# Omniband.net
KiCad netlist of a schematic drawn in EAGLE
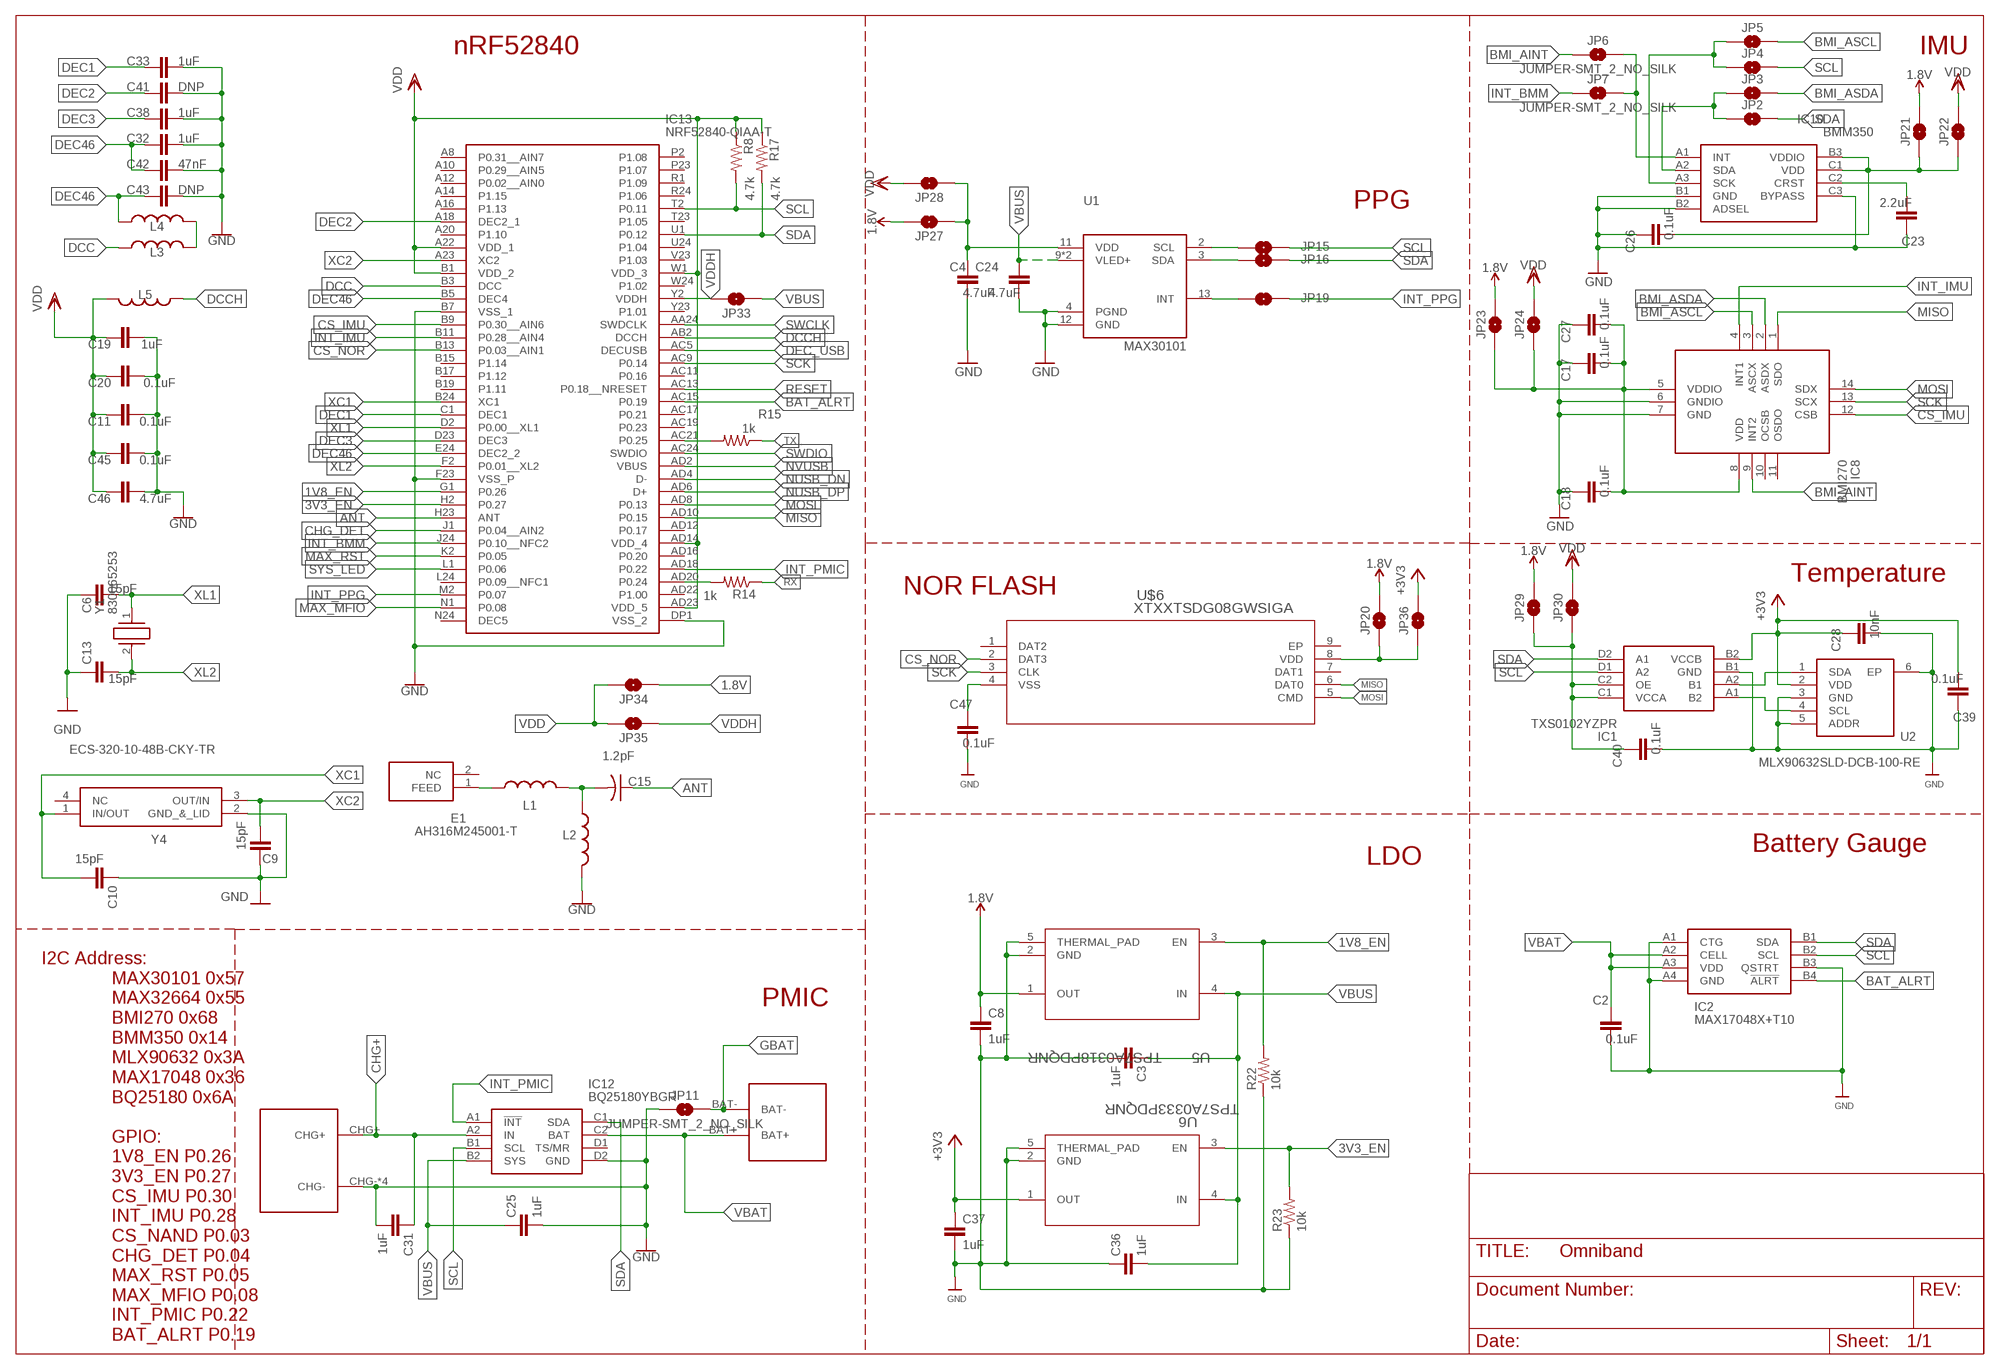
[diagram p0: schematic, sheet 1, part 1 of 2]
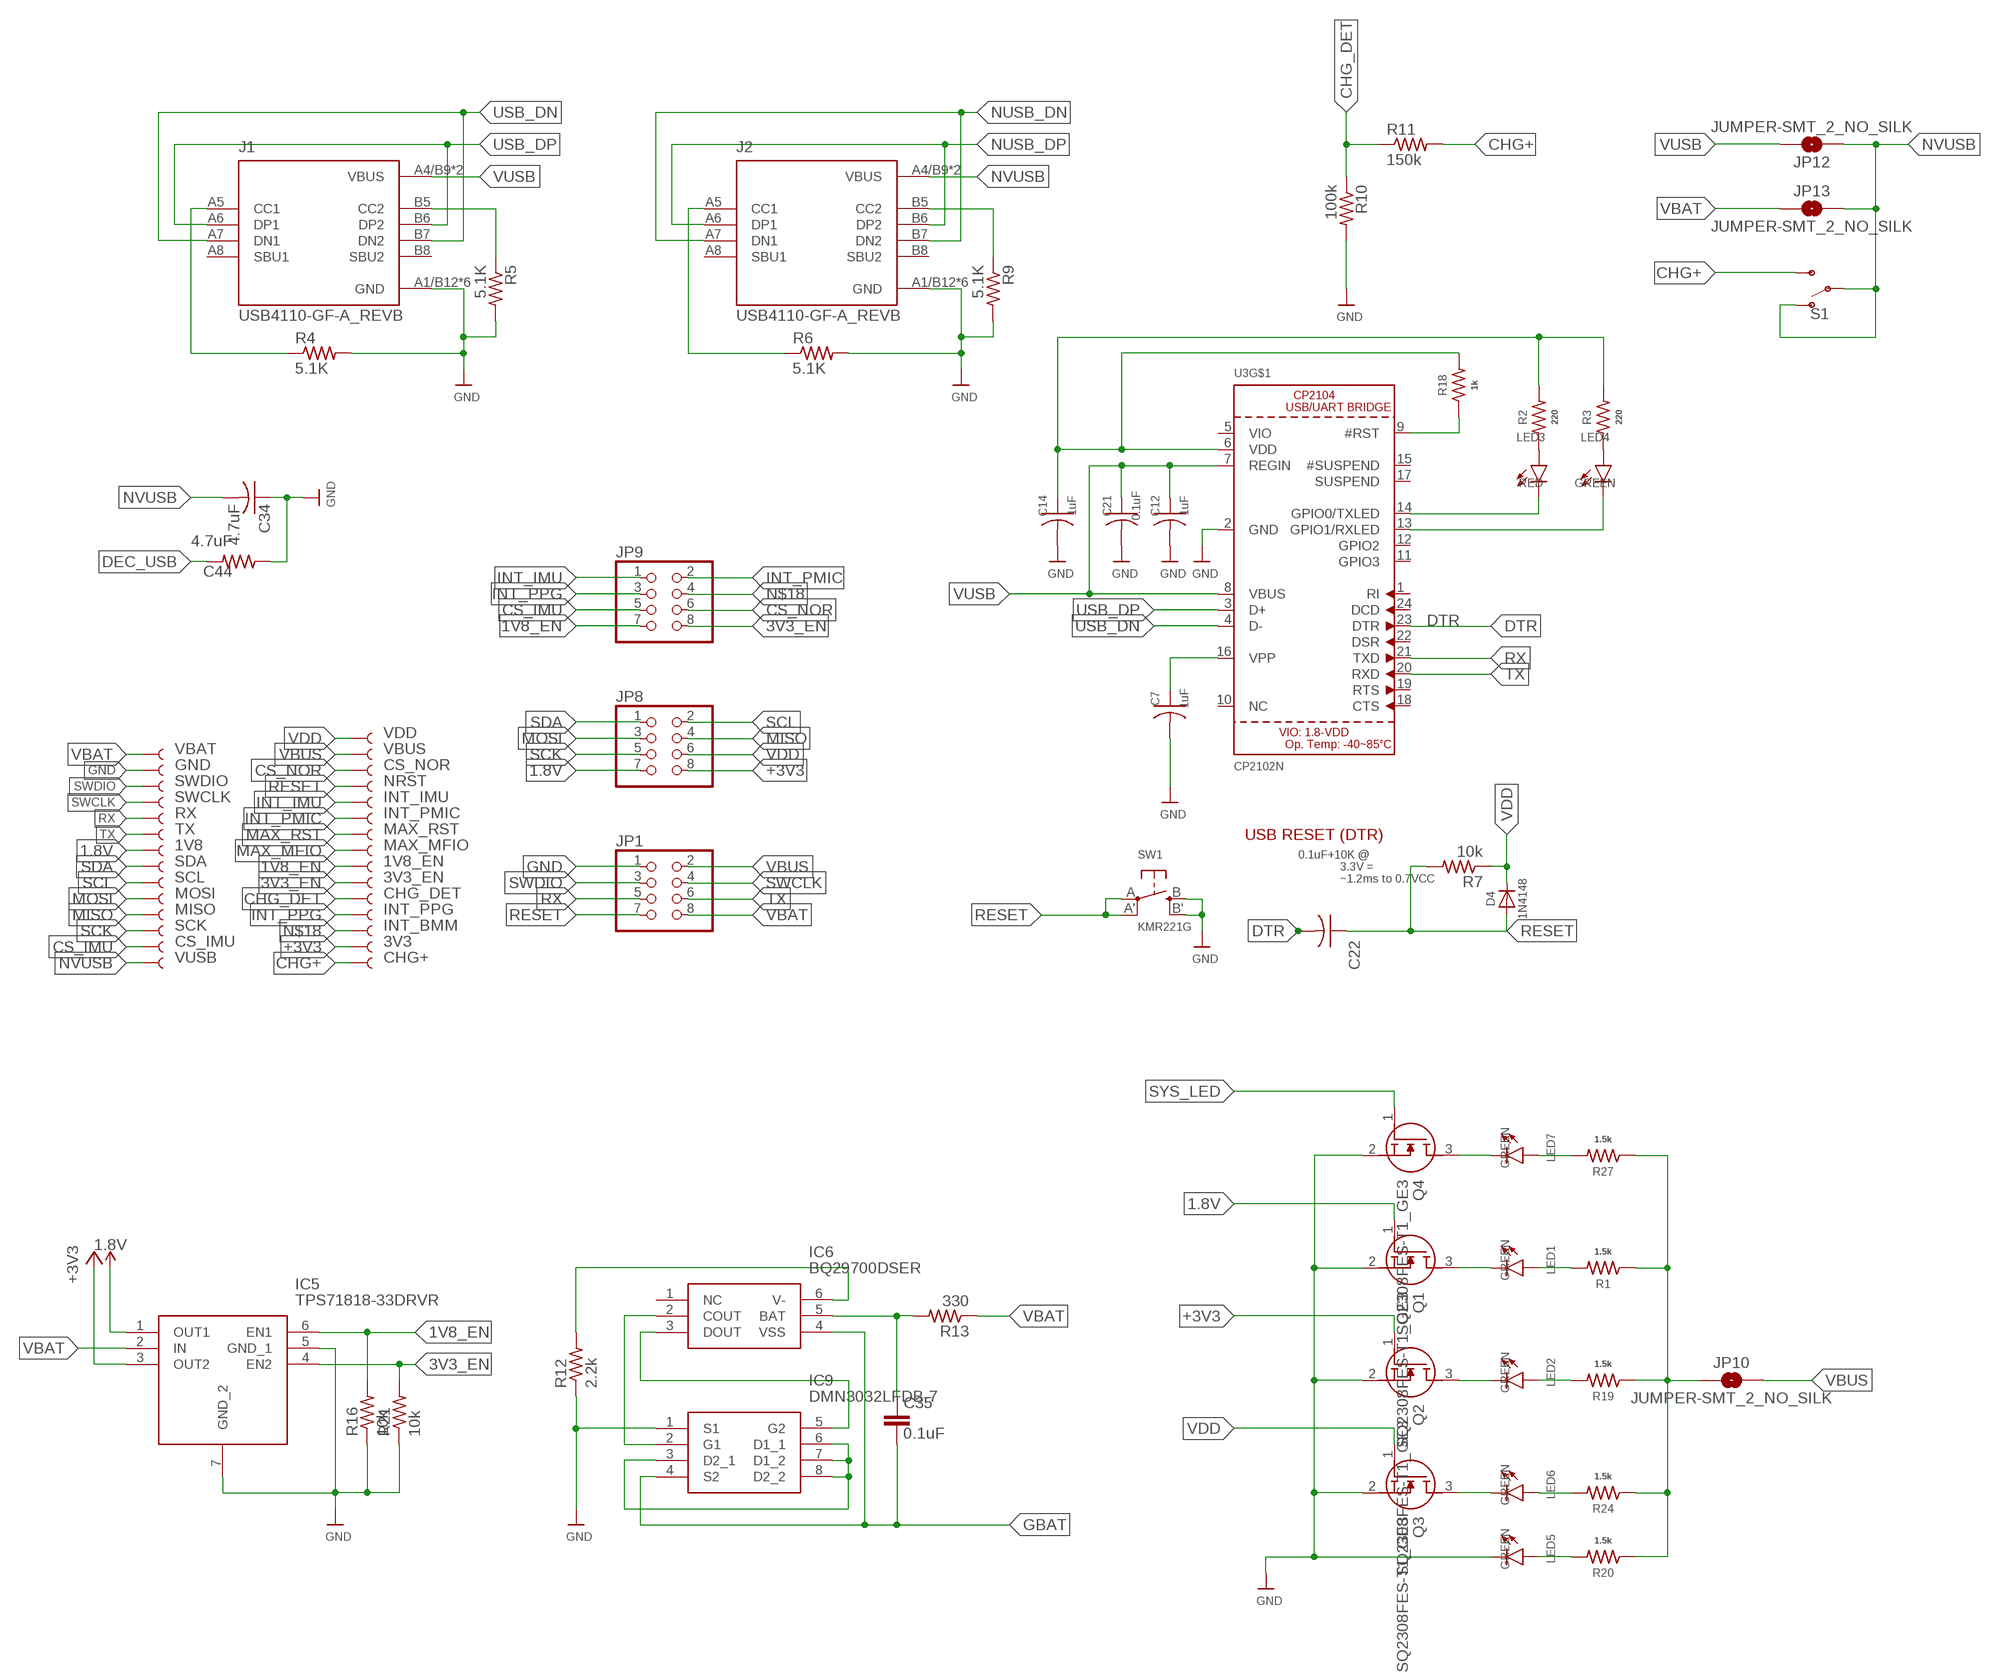
[diagram p1: schematic, sheet 1, part 2 of 2]

(export (version "E")
  (design (tool "Eeschema 10.0.6"))
  (components
    (comp (ref "1V8")
      (value "TEST-POINT3")
      (footprint "eagle-import:PAD.03X.03")
      (libsource (lib "eagle-import") (part "TEST-POINT3"))
    )
    (comp (ref "1V8_EN")
      (value "TEST-POINT3")
      (footprint "eagle-import:PAD.03X.03")
      (libsource (lib "eagle-import") (part "TEST-POINT3"))
    )
    (comp (ref "3V3")
      (value "TEST-POINT3")
      (footprint "eagle-import:PAD.03X.03")
      (libsource (lib "eagle-import") (part "TEST-POINT3"))
    )
    (comp (ref "3V3_EN")
      (value "TEST-POINT3")
      (footprint "eagle-import:PAD.03X.03")
      (libsource (lib "eagle-import") (part "TEST-POINT3"))
    )
    (comp (ref "C2")
      (value "0.1uF")
      (footprint "eagle-import:C0201")
      (libsource (lib "eagle-import") (part "C-EUC0201"))
    )
    (comp (ref "C3")
      (value "1uF")
      (footprint "eagle-import:C0201")
      (libsource (lib "eagle-import") (part "C-EUC0201"))
    )
    (comp (ref "C4")
      (value "4.7uF")
      (footprint "eagle-import:C0201")
      (libsource (lib "eagle-import") (part "C-EUC0201"))
    )
    (comp (ref "C6")
      (value "15pF")
      (footprint "eagle-import:C0201")
      (libsource (lib "eagle-import") (part "C-EUC0201"))
    )
    (comp (ref "C7")
      (value "1uF")
      (footprint "eagle-import:C0603")
      (libsource (lib "eagle-import") (part "C-USC0603"))
    )
    (comp (ref "C8")
      (value "1uF")
      (footprint "eagle-import:C0201")
      (libsource (lib "eagle-import") (part "C-EUC0201"))
    )
    (comp (ref "C9")
      (value "15pF")
      (footprint "eagle-import:C0201")
      (libsource (lib "eagle-import") (part "C-EUC0201"))
    )
    (comp (ref "C10")
      (value "15pF")
      (footprint "eagle-import:C0201")
      (libsource (lib "eagle-import") (part "C-EUC0201"))
    )
    (comp (ref "C11")
      (value "0.1uF")
      (footprint "eagle-import:C0201")
      (libsource (lib "eagle-import") (part "C-EUC0201"))
    )
    (comp (ref "C12")
      (value "1uF")
      (footprint "eagle-import:C0603")
      (libsource (lib "eagle-import") (part "C-USC0603"))
    )
    (comp (ref "C13")
      (value "15pF")
      (footprint "eagle-import:C0201")
      (libsource (lib "eagle-import") (part "C-EUC0201"))
    )
    (comp (ref "C14")
      (value "1uF")
      (footprint "eagle-import:C0603")
      (libsource (lib "eagle-import") (part "C-USC0603"))
    )
    (comp (ref "C15")
      (value "1.2pF")
      (footprint "eagle-import:C0201")
      (libsource (lib "eagle-import") (part "C-USC0201"))
    )
    (comp (ref "C17")
      (value "0.1uF")
      (footprint "eagle-import:C0201")
      (libsource (lib "eagle-import") (part "C-EUC0201"))
    )
    (comp (ref "C18")
      (value "0.1uF")
      (footprint "eagle-import:C0201")
      (libsource (lib "eagle-import") (part "C-EUC0201"))
    )
    (comp (ref "C19")
      (value "1uF")
      (footprint "eagle-import:C0201")
      (libsource (lib "eagle-import") (part "C-EUC0201"))
    )
    (comp (ref "C20")
      (value "0.1uF")
      (footprint "eagle-import:C0201")
      (libsource (lib "eagle-import") (part "C-EUC0201"))
    )
    (comp (ref "C21")
      (value "0.1uF")
      (footprint "eagle-import:C0603")
      (libsource (lib "eagle-import") (part "C-USC0603"))
    )
    (comp (ref "C22")
      (value "220nF")
      (footprint "eagle-import:C0603")
      (libsource (lib "eagle-import") (part "C-USC0603"))
    )
    (comp (ref "C23")
      (value "2.2uF")
      (footprint "eagle-import:C0201")
      (libsource (lib "eagle-import") (part "C-EUC0201"))
    )
    (comp (ref "C24")
      (value "4.7uF")
      (footprint "eagle-import:C0201")
      (libsource (lib "eagle-import") (part "C-EUC0201"))
    )
    (comp (ref "C25")
      (value "1uF")
      (footprint "eagle-import:C0201")
      (libsource (lib "eagle-import") (part "C-EUC0201"))
    )
    (comp (ref "C26")
      (value "0.1uF")
      (footprint "eagle-import:C0201")
      (libsource (lib "eagle-import") (part "C-EUC0201"))
    )
    (comp (ref "C27")
      (value "0.1uF")
      (footprint "eagle-import:C0201")
      (libsource (lib "eagle-import") (part "C-EUC0201"))
    )
    (comp (ref "C28")
      (value "10nF")
      (footprint "eagle-import:C0201")
      (libsource (lib "eagle-import") (part "C-EUC0201"))
    )
    (comp (ref "C31")
      (value "1uF")
      (footprint "eagle-import:C0201")
      (libsource (lib "eagle-import") (part "C-EUC0201"))
    )
    (comp (ref "C32")
      (value "1uF")
      (footprint "eagle-import:C0201")
      (libsource (lib "eagle-import") (part "C-EUC0201"))
    )
    (comp (ref "C33")
      (value "1uF")
      (footprint "eagle-import:C0201")
      (libsource (lib "eagle-import") (part "C-EUC0201"))
    )
    (comp (ref "C34")
      (value "4.7uF")
      (footprint "eagle-import:C0603")
      (libsource (lib "eagle-import") (part "C-USC0603"))
    )
    (comp (ref "C35")
      (value "0.1uF")
      (footprint "eagle-import:C0201")
      (libsource (lib "eagle-import") (part "C-EUC0201"))
    )
    (comp (ref "C36")
      (value "1uF")
      (footprint "eagle-import:C0201")
      (libsource (lib "eagle-import") (part "C-EUC0201"))
    )
    (comp (ref "C37")
      (value "1uF")
      (footprint "eagle-import:C0201")
      (libsource (lib "eagle-import") (part "C-EUC0201"))
    )
    (comp (ref "C38")
      (value "1uF")
      (footprint "eagle-import:C0201")
      (libsource (lib "eagle-import") (part "C-EUC0201"))
    )
    (comp (ref "C39")
      (value "0.1uF")
      (footprint "eagle-import:C0201")
      (libsource (lib "eagle-import") (part "C-EUC0201"))
    )
    (comp (ref "C40")
      (value "0.1uF")
      (footprint "eagle-import:C0201")
      (libsource (lib "eagle-import") (part "C-EUC0201"))
    )
    (comp (ref "C41")
      (value "DNP")
      (footprint "eagle-import:C0201")
      (libsource (lib "eagle-import") (part "C-EUC0201"))
    )
    (comp (ref "C42")
      (value "47nF")
      (footprint "eagle-import:C0201")
      (libsource (lib "eagle-import") (part "C-EUC0201"))
    )
    (comp (ref "C43")
      (value "DNP")
      (footprint "eagle-import:C0201")
      (libsource (lib "eagle-import") (part "C-EUC0201"))
    )
    (comp (ref "C44")
      (value "4.7uF")
      (footprint "eagle-import:R0201")
      (libsource (lib "eagle-import") (part "R-US_R0201"))
    )
    (comp (ref "C45")
      (value "0.1uF")
      (footprint "eagle-import:C0201")
      (libsource (lib "eagle-import") (part "C-EUC0201"))
    )
    (comp (ref "C46")
      (value "4.7uF")
      (footprint "eagle-import:C0201")
      (libsource (lib "eagle-import") (part "C-EUC0201"))
    )
    (comp (ref "C47")
      (value "0.1uF")
      (footprint "eagle-import:C0201")
      (libsource (lib "eagle-import") (part "C-EUC0201"))
    )
    (comp (ref "CHG+")
      (value "TEST-POINT3")
      (footprint "eagle-import:PAD.03X.03")
      (libsource (lib "eagle-import") (part "TEST-POINT3"))
    )
    (comp (ref "CHG_DET")
      (value "TEST-POINT3")
      (footprint "eagle-import:PAD.03X.03")
      (libsource (lib "eagle-import") (part "TEST-POINT3"))
    )
    (comp (ref "CS_IMU")
      (value "TEST-POINT3")
      (footprint "eagle-import:PAD.03X.03")
      (libsource (lib "eagle-import") (part "TEST-POINT3"))
    )
    (comp (ref "CS_NOR")
      (value "TEST-POINT3")
      (footprint "eagle-import:PAD.03X.03")
      (libsource (lib "eagle-import") (part "TEST-POINT3"))
    )
    (comp (ref "D4")
      (value "1N4148")
      (footprint "eagle-import:SOD-323")
      (libsource (lib "eagle-import") (part "DIODESOD-323"))
    )
    (comp (ref "E1")
      (value "AH316M245001-T")
      (footprint "eagle-import:ANTC3216X60N")
      (fields (field (name "MOUSER_PART_NUMBER") "963-AH316M245001-T"))
      (libsource (lib "eagle-import") (part "AH316M245001-T"))
    )
    (comp (ref "GND")
      (value "TEST-POINT3")
      (footprint "eagle-import:PAD.03X.03")
      (libsource (lib "eagle-import") (part "TEST-POINT3"))
    )
    (comp (ref "IC1")
      (value "TXS0102YZPR")
      (footprint "eagle-import:BGA8C50P2X4_89X189X50")
      (fields (field (name "MOUSER_PART_NUMBER") "595-TXS0102YZPR"))
      (libsource (lib "eagle-import") (part "TXS0102YZPR"))
    )
    (comp (ref "IC2")
      (value "MAX17048X+T10")
      (footprint "eagle-import:BGA8C40P4X2_167X93X69")
      (fields (field (name "MOUSER_PART_NUMBER") "700-MAX17048X+T10"))
      (libsource (lib "eagle-import") (part "MAX17048X+T10"))
    )
    (comp (ref "IC5")
      (value "TPS71818-33DRVR")
      (footprint "eagle-import:SON65P200X200X80-7N")
      (libsource (lib "eagle-import") (part "TPS71818-33DRVR"))
    )
    (comp (ref "IC6")
      (value "BQ29700DSER")
      (footprint "eagle-import:SON50P150X150X80-6N")
      (fields (field (name "MOUSER_PART_NUMBER") "595-BQ29700DSER"))
      (libsource (lib "eagle-import") (part "BQ29700DSER"))
    )
    (comp (ref "IC8")
      (value "BMI270")
      (footprint "eagle-import:BMI270")
      (fields (field (name "MOUSER_PART_NUMBER") "262-BMI270"))
      (libsource (lib "eagle-import") (part "BMI270"))
    )
    (comp (ref "IC9")
      (value "DMN3032LFDB-7")
      (footprint "eagle-import:DMP1046UFDB7")
      (fields (field (name "MOUSER_PART_NUMBER") "621-DMN3032LFDB-7"))
      (libsource (lib "eagle-import") (part "DMN3032LFDB-7"))
    )
    (comp (ref "IC10")
      (value "BMM350")
      (footprint "eagle-import:BGA9C40P3X3_128X128X54")
      (fields (field (name "MOUSER_PART_NUMBER") "262-BMM350"))
      (libsource (lib "eagle-import") (part "BMM350"))
    )
    (comp (ref "IC12")
      (value "BQ25180YBGR")
      (footprint "eagle-import:BGA8C40P2X4_100X155X50")
      (fields (field (name "MOUSER_PART_NUMBER") "595-BQ25180YBGR"))
      (libsource (lib "eagle-import") (part "BQ25180YBGR"))
    )
    (comp (ref "IC13")
      (value "NRF52840-QIAA-T")
      (footprint "eagle-import:NRF52840QIAAT")
      (fields
        (field (name "MANUFACTURER_PART_NUMBER") "nRF52840-QIAA-T")
        (field (name "MOUSER_PART_NUMBER") "949-NRF52840-QIAA-T")
      )
      (libsource (lib "eagle-import") (part "NRF52840-QIAA-T"))
    )
    (comp (ref "INT_BMM")
      (value "TEST-POINT3")
      (footprint "eagle-import:PAD.03X.03")
      (libsource (lib "eagle-import") (part "TEST-POINT3"))
    )
    (comp (ref "INT_IMU")
      (value "TEST-POINT3")
      (footprint "eagle-import:PAD.03X.03")
      (libsource (lib "eagle-import") (part "TEST-POINT3"))
    )
    (comp (ref "INT_PMIC")
      (value "TEST-POINT3")
      (footprint "eagle-import:PAD.03X.03")
      (libsource (lib "eagle-import") (part "TEST-POINT3"))
    )
    (comp (ref "INT_PPG")
      (value "TEST-POINT3")
      (footprint "eagle-import:PAD.03X.03")
      (libsource (lib "eagle-import") (part "TEST-POINT3"))
    )
    (comp (ref "J1")
      (value "USB4110-GF-A_REVB")
      (footprint "eagle-import:GCT_USB4110-GF-A_REVB")
      (fields (field (name "MF") "GCT") (field (name "MP") "USB4110-GF-A"))
      (libsource (lib "eagle-import") (part "USB4110-GF-A_REVB"))
    )
    (comp (ref "J2")
      (value "USB4110-GF-A_REVB")
      (footprint "eagle-import:GCT_USB4110-GF-A_REVB")
      (fields (field (name "MF") "GCT") (field (name "MP") "USB4110-GF-A"))
      (libsource (lib "eagle-import") (part "USB4110-GF-A_REVB"))
    )
    (comp (ref "JP1")
      (value "PINHD-2X4")
      (footprint "eagle-import:2X04")
      (libsource (lib "eagle-import") (part "PINHD-2X4"))
    )
    (comp (ref "JP2")
      (value "JUMPER-SMT_2_NO_SILK")
      (footprint "eagle-import:SMT-JUMPER_2_NO_SILK")
      (libsource (lib "eagle-import") (part "JUMPER-SMT_2_NO_SILK"))
    )
    (comp (ref "JP3")
      (value "JUMPER-SMT_2_NO_SILK")
      (footprint "eagle-import:SMT-JUMPER_2_NO_SILK")
      (libsource (lib "eagle-import") (part "JUMPER-SMT_2_NO_SILK"))
    )
    (comp (ref "JP4")
      (value "JUMPER-SMT_2_NO_SILK")
      (footprint "eagle-import:SMT-JUMPER_2_NO_SILK")
      (libsource (lib "eagle-import") (part "JUMPER-SMT_2_NO_SILK"))
    )
    (comp (ref "JP5")
      (value "JUMPER-SMT_2_NO_SILK")
      (footprint "eagle-import:SMT-JUMPER_2_NO_SILK")
      (libsource (lib "eagle-import") (part "JUMPER-SMT_2_NO_SILK"))
    )
    (comp (ref "JP6")
      (value "JUMPER-SMT_2_NO_SILK")
      (footprint "eagle-import:SMT-JUMPER_2_NO_SILK")
      (libsource (lib "eagle-import") (part "JUMPER-SMT_2_NO_SILK"))
    )
    (comp (ref "JP7")
      (value "JUMPER-SMT_2_NO_SILK")
      (footprint "eagle-import:SMT-JUMPER_2_NO_SILK")
      (libsource (lib "eagle-import") (part "JUMPER-SMT_2_NO_SILK"))
    )
    (comp (ref "JP8")
      (value "PINHD-2X4")
      (footprint "eagle-import:2X04")
      (libsource (lib "eagle-import") (part "PINHD-2X4"))
    )
    (comp (ref "JP9")
      (value "PINHD-2X4")
      (footprint "eagle-import:2X04")
      (libsource (lib "eagle-import") (part "PINHD-2X4"))
    )
    (comp (ref "JP10")
      (value "JUMPER-SMT_2_NO_SILK")
      (footprint "eagle-import:SMT-JUMPER_2_NO_SILK")
      (libsource (lib "eagle-import") (part "JUMPER-SMT_2_NO_SILK"))
    )
    (comp (ref "JP11")
      (value "JUMPER-SMT_2_NO_SILK")
      (footprint "eagle-import:SMT-JUMPER_2_NO_SILK")
      (libsource (lib "eagle-import") (part "JUMPER-SMT_2_NO_SILK"))
    )
    (comp (ref "JP12")
      (value "JUMPER-SMT_2_NO_SILK")
      (footprint "eagle-import:SMT-JUMPER_2_NO_SILK")
      (libsource (lib "eagle-import") (part "JUMPER-SMT_2_NO_SILK"))
    )
    (comp (ref "JP13")
      (value "JUMPER-SMT_2_NO_SILK")
      (footprint "eagle-import:SMT-JUMPER_2_NO_SILK")
      (libsource (lib "eagle-import") (part "JUMPER-SMT_2_NO_SILK"))
    )
    (comp (ref "JP15")
      (value "JUMPER-SMT_2_NO_SILK")
      (footprint "eagle-import:SMT-JUMPER_2_NO_SILK")
      (libsource (lib "eagle-import") (part "JUMPER-SMT_2_NO_SILK"))
    )
    (comp (ref "JP16")
      (value "JUMPER-SMT_2_NO_SILK")
      (footprint "eagle-import:SMT-JUMPER_2_NO_SILK")
      (libsource (lib "eagle-import") (part "JUMPER-SMT_2_NO_SILK"))
    )
    (comp (ref "JP19")
      (value "JUMPER-SMT_2_NO_SILK")
      (footprint "eagle-import:SMT-JUMPER_2_NO_SILK")
      (libsource (lib "eagle-import") (part "JUMPER-SMT_2_NO_SILK"))
    )
    (comp (ref "JP20")
      (value "JUMPER-SMT_2_NO_SILK")
      (footprint "eagle-import:SMT-JUMPER_2_NO_SILK")
      (libsource (lib "eagle-import") (part "JUMPER-SMT_2_NO_SILK"))
    )
    (comp (ref "JP21")
      (value "JUMPER-SMT_2_NO_SILK")
      (footprint "eagle-import:SMT-JUMPER_2_NO_SILK")
      (libsource (lib "eagle-import") (part "JUMPER-SMT_2_NO_SILK"))
    )
    (comp (ref "JP22")
      (value "JUMPER-SMT_2_NO_SILK")
      (footprint "eagle-import:SMT-JUMPER_2_NO_SILK")
      (libsource (lib "eagle-import") (part "JUMPER-SMT_2_NO_SILK"))
    )
    (comp (ref "JP23")
      (value "JUMPER-SMT_2_NO_SILK")
      (footprint "eagle-import:SMT-JUMPER_2_NO_SILK")
      (libsource (lib "eagle-import") (part "JUMPER-SMT_2_NO_SILK"))
    )
    (comp (ref "JP24")
      (value "JUMPER-SMT_2_NO_SILK")
      (footprint "eagle-import:SMT-JUMPER_2_NO_SILK")
      (libsource (lib "eagle-import") (part "JUMPER-SMT_2_NO_SILK"))
    )
    (comp (ref "JP27")
      (value "JUMPER-SMT_2_NO_SILK")
      (footprint "eagle-import:SMT-JUMPER_2_NO_SILK")
      (libsource (lib "eagle-import") (part "JUMPER-SMT_2_NO_SILK"))
    )
    (comp (ref "JP28")
      (value "JUMPER-SMT_2_NO_SILK")
      (footprint "eagle-import:SMT-JUMPER_2_NO_SILK")
      (libsource (lib "eagle-import") (part "JUMPER-SMT_2_NO_SILK"))
    )
    (comp (ref "JP29")
      (value "JUMPER-SMT_2_NO_SILK")
      (footprint "eagle-import:SMT-JUMPER_2_NO_SILK")
      (libsource (lib "eagle-import") (part "JUMPER-SMT_2_NO_SILK"))
    )
    (comp (ref "JP30")
      (value "JUMPER-SMT_2_NO_SILK")
      (footprint "eagle-import:SMT-JUMPER_2_NO_SILK")
      (libsource (lib "eagle-import") (part "JUMPER-SMT_2_NO_SILK"))
    )
    (comp (ref "JP33")
      (value "JUMPER-SMT_2_NO_SILK")
      (footprint "eagle-import:SMT-JUMPER_2_NO_SILK")
      (libsource (lib "eagle-import") (part "JUMPER-SMT_2_NO_SILK"))
    )
    (comp (ref "JP34")
      (value "JUMPER-SMT_2_NO_SILK")
      (footprint "eagle-import:SMT-JUMPER_2_NO_SILK")
      (libsource (lib "eagle-import") (part "JUMPER-SMT_2_NO_SILK"))
    )
    (comp (ref "JP35")
      (value "JUMPER-SMT_2_NO_SILK")
      (footprint "eagle-import:SMT-JUMPER_2_NO_SILK")
      (libsource (lib "eagle-import") (part "JUMPER-SMT_2_NO_SILK"))
    )
    (comp (ref "JP36")
      (value "JUMPER-SMT_2_NO_SILK")
      (footprint "eagle-import:SMT-JUMPER_2_NO_SILK")
      (libsource (lib "eagle-import") (part "JUMPER-SMT_2_NO_SILK"))
    )
    (comp (ref "L1")
      (value "3.3nH")
      (footprint "eagle-import:L0201")
      (libsource (lib "eagle-import") (part "L-USL0201"))
    )
    (comp (ref "L2")
      (value "2.7nH")
      (footprint "eagle-import:L0201")
      (libsource (lib "eagle-import") (part "L-USL0201"))
    )
    (comp (ref "L3")
      (value "10uH")
      (footprint "eagle-import:L0201")
      (libsource (lib "eagle-import") (part "L-USL0201"))
    )
    (comp (ref "L4")
      (value "15nH")
      (footprint "eagle-import:L0201")
      (libsource (lib "eagle-import") (part "L-USL0201"))
    )
    (comp (ref "L5")
      (value "2.7nH")
      (footprint "eagle-import:L0201")
      (libsource (lib "eagle-import") (part "L-USL0201"))
    )
    (comp (ref "LED1")
      (value "GREEN")
      (footprint "eagle-import:CHIPLED_0603")
      (libsource (lib "eagle-import") (part "LEDCHIPLED_0603"))
    )
    (comp (ref "LED2")
      (value "GREEN")
      (footprint "eagle-import:CHIPLED_0603")
      (libsource (lib "eagle-import") (part "LEDCHIPLED_0603"))
    )
    (comp (ref "LED3")
      (value "RED")
      (footprint "eagle-import:CHIPLED_0603")
      (libsource (lib "eagle-import") (part "LEDCHIPLED_0603"))
    )
    (comp (ref "LED4")
      (value "GREEN")
      (footprint "eagle-import:CHIPLED_0603")
      (libsource (lib "eagle-import") (part "LEDCHIPLED_0603"))
    )
    (comp (ref "LED5")
      (value "GREEN")
      (footprint "eagle-import:CHIPLED_0603")
      (libsource (lib "eagle-import") (part "LEDCHIPLED_0603"))
    )
    (comp (ref "LED6")
      (value "GREEN")
      (footprint "eagle-import:CHIPLED_0603")
      (libsource (lib "eagle-import") (part "LEDCHIPLED_0603"))
    )
    (comp (ref "LED7")
      (value "GREEN")
      (footprint "eagle-import:CHIPLED_0603")
      (libsource (lib "eagle-import") (part "LEDCHIPLED_0603"))
    )
    (comp (ref "MAX_MFIO")
      (value "TEST-POINT3")
      (footprint "eagle-import:PAD.03X.03")
      (libsource (lib "eagle-import") (part "TEST-POINT3"))
    )
    (comp (ref "MAX_RST")
      (value "TEST-POINT3")
      (footprint "eagle-import:PAD.03X.03")
      (libsource (lib "eagle-import") (part "TEST-POINT3"))
    )
    (comp (ref "MISO")
      (value "TEST-POINT3")
      (footprint "eagle-import:PAD.03X.03")
      (libsource (lib "eagle-import") (part "TEST-POINT3"))
    )
    (comp (ref "MOSI")
      (value "TEST-POINT3")
      (footprint "eagle-import:PAD.03X.03")
      (libsource (lib "eagle-import") (part "TEST-POINT3"))
    )
    (comp (ref "NRST")
      (value "TEST-POINT3")
      (footprint "eagle-import:PAD.03X.03")
      (libsource (lib "eagle-import") (part "TEST-POINT3"))
    )
    (comp (ref "Q1")
      (value "SQ2308FES-T1_GE3")
      (footprint "eagle-import:SOT95P237X112-3N")
      (fields (field (name "MOUSER_PART_NUMBER") "78-SQ2308FES-T1_GE3"))
      (libsource (lib "eagle-import") (part "SQ2308FES-T1_GE3"))
    )
    (comp (ref "Q2")
      (value "SQ2308FES-T1_GE3")
      (footprint "eagle-import:SOT95P237X112-3N")
      (fields (field (name "MOUSER_PART_NUMBER") "78-SQ2308FES-T1_GE3"))
      (libsource (lib "eagle-import") (part "SQ2308FES-T1_GE3"))
    )
    (comp (ref "Q3")
      (value "SQ2308FES-T1_GE3")
      (footprint "eagle-import:SOT95P237X112-3N")
      (fields (field (name "MOUSER_PART_NUMBER") "78-SQ2308FES-T1_GE3"))
      (libsource (lib "eagle-import") (part "SQ2308FES-T1_GE3"))
    )
    (comp (ref "Q4")
      (value "SQ2308FES-T1_GE3")
      (footprint "eagle-import:SOT95P237X112-3N")
      (fields (field (name "MOUSER_PART_NUMBER") "78-SQ2308FES-T1_GE3"))
      (libsource (lib "eagle-import") (part "SQ2308FES-T1_GE3"))
    )
    (comp (ref "R1")
      (value "1.5k")
      (footprint "eagle-import:R0603")
      (libsource (lib "eagle-import") (part "R-US_R0603"))
    )
    (comp (ref "R2")
      (value "220")
      (footprint "eagle-import:R0603")
      (libsource (lib "eagle-import") (part "R-US_R0603"))
    )
    (comp (ref "R3")
      (value "220")
      (footprint "eagle-import:R0603")
      (libsource (lib "eagle-import") (part "R-US_R0603"))
    )
    (comp (ref "R4")
      (value "5.1K")
      (footprint "eagle-import:R0603")
      (libsource (lib "eagle-import") (part "R-US_R0603"))
    )
    (comp (ref "R5")
      (value "5.1K")
      (footprint "eagle-import:R0603")
      (libsource (lib "eagle-import") (part "R-US_R0603"))
    )
    (comp (ref "R6")
      (value "5.1K")
      (footprint "eagle-import:R0603")
      (libsource (lib "eagle-import") (part "R-US_R0603"))
    )
    (comp (ref "R7")
      (value "10k")
      (footprint "eagle-import:R0603")
      (libsource (lib "eagle-import") (part "R-US_R0603"))
    )
    (comp (ref "R8")
      (value "4.7k")
      (footprint "eagle-import:R0201")
      (libsource (lib "eagle-import") (part "R-US_R0201"))
    )
    (comp (ref "R9")
      (value "5.1K")
      (footprint "eagle-import:R0603")
      (libsource (lib "eagle-import") (part "R-US_R0603"))
    )
    (comp (ref "R10")
      (value "100k")
      (footprint "eagle-import:R0603")
      (libsource (lib "eagle-import") (part "R-US_R0603"))
    )
    (comp (ref "R11")
      (value "150k")
      (footprint "eagle-import:R0603")
      (libsource (lib "eagle-import") (part "R-US_R0603"))
    )
    (comp (ref "R12")
      (value "2.2k")
      (footprint "eagle-import:R0201")
      (libsource (lib "eagle-import") (part "R-US_R0201"))
    )
    (comp (ref "R13")
      (value "330")
      (footprint "eagle-import:R0201")
      (libsource (lib "eagle-import") (part "R-US_R0201"))
    )
    (comp (ref "R14")
      (value "1k")
      (footprint "eagle-import:R0201")
      (libsource (lib "eagle-import") (part "R-US_R0201"))
    )
    (comp (ref "R15")
      (value "1k")
      (footprint "eagle-import:R0201")
      (libsource (lib "eagle-import") (part "R-US_R0201"))
    )
    (comp (ref "R16")
      (value "10k")
      (footprint "eagle-import:R0201")
      (libsource (lib "eagle-import") (part "R-US_R0201"))
    )
    (comp (ref "R17")
      (value "4.7k")
      (footprint "eagle-import:R0201")
      (libsource (lib "eagle-import") (part "R-US_R0201"))
    )
    (comp (ref "R18")
      (value "1k")
      (footprint "eagle-import:R0603")
      (libsource (lib "eagle-import") (part "R-US_R0603"))
    )
    (comp (ref "R19")
      (value "1.5k")
      (footprint "eagle-import:R0603")
      (libsource (lib "eagle-import") (part "R-US_R0603"))
    )
    (comp (ref "R20")
      (value "1.5k")
      (footprint "eagle-import:R0603")
      (libsource (lib "eagle-import") (part "R-US_R0603"))
    )
    (comp (ref "R21")
      (value "10k")
      (footprint "eagle-import:R0201")
      (libsource (lib "eagle-import") (part "R-US_R0201"))
    )
    (comp (ref "R22")
      (value "10k")
      (footprint "eagle-import:R0201")
      (libsource (lib "eagle-import") (part "R-US_R0201"))
    )
    (comp (ref "R23")
      (value "10k")
      (footprint "eagle-import:R0201")
      (libsource (lib "eagle-import") (part "R-US_R0201"))
    )
    (comp (ref "R24")
      (value "1.5k")
      (footprint "eagle-import:R0603")
      (libsource (lib "eagle-import") (part "R-US_R0603"))
    )
    (comp (ref "R27")
      (value "1.5k")
      (footprint "eagle-import:R0603")
      (libsource (lib "eagle-import") (part "R-US_R0603"))
    )
    (comp (ref "RX")
      (value "TEST-POINT3")
      (footprint "eagle-import:PAD.03X.03")
      (libsource (lib "eagle-import") (part "TEST-POINT3"))
    )
    (comp (ref "S1")
      (value "SWITCH-SPDT-SMD-RIGHT-ANGLE")
      (footprint "eagle-import:SWITCH_SPST_SMD_A")
      (libsource (lib "eagle-import") (part "SWITCH-SPDT-SMD-RIGHT-ANGLE"))
    )
    (comp (ref "SCK")
      (value "TEST-POINT3")
      (footprint "eagle-import:PAD.03X.03")
      (libsource (lib "eagle-import") (part "TEST-POINT3"))
    )
    (comp (ref "SCL")
      (value "TEST-POINT3")
      (footprint "eagle-import:PAD.03X.03")
      (libsource (lib "eagle-import") (part "TEST-POINT3"))
    )
    (comp (ref "SDA")
      (value "TEST-POINT3")
      (footprint "eagle-import:PAD.03X.03")
      (libsource (lib "eagle-import") (part "TEST-POINT3"))
    )
    (comp (ref "SW1")
      (value "KMR221G")
      (footprint "eagle-import:BTN_KMR2_4.6X2.8")
      (libsource (lib "eagle-import") (part "SWITCH_TACT_SMT4.6X2.8"))
    )
    (comp (ref "SWCLK")
      (value "TEST-POINT3")
      (footprint "eagle-import:PAD.03X.03")
      (libsource (lib "eagle-import") (part "TEST-POINT3"))
    )
    (comp (ref "SWDIO")
      (value "TEST-POINT3")
      (footprint "eagle-import:PAD.03X.03")
      (libsource (lib "eagle-import") (part "TEST-POINT3"))
    )
    (comp (ref "TX")
      (value "TEST-POINT3")
      (footprint "eagle-import:PAD.03X.03")
      (libsource (lib "eagle-import") (part "TEST-POINT3"))
    )
    (comp (ref "U$3")
      (value "GRP160722")
      (footprint "eagle-import:GRP160722")
      (libsource (lib "eagle-import") (part "GRP160722"))
    )
    (comp (ref "U$6")
      (value "XTXXTSDG08GWSIGA")
      (footprint "eagle-import:WNG008_SPA")
      (libsource (lib "eagle-import") (part "XTXXTSDG08GWSIGA"))
    )
    (comp (ref "U$8")
      (value "CX-4MM-JZ")
      (footprint "eagle-import:CX-4MM-JZ")
      (libsource (lib "eagle-import") (part "CX-4MM-JZ"))
    )
    (comp (ref "U1")
      (value "MAX30101")
      (footprint "eagle-import:MAX30100")
      (fields (field (name "PARTNO") "AS-ITM-00473"))
      (libsource (lib "eagle-import") (part "AS-ITM-00473"))
    )
    (comp (ref "U2")
      (value "MLX90632SLD-DCB-100-RE")
      (footprint "eagle-import:MLX90632SLDDCB100RE")
      (fields (field (name "MOUSER_PART_NUMBER") "482-90632SLDDCB100RE"))
      (libsource (lib "eagle-import") (part "MLX90632SLD-DCB-100-RE"))
    )
    (comp (ref "U3")
      (value "CP2102N")
      (footprint "eagle-import:QFN24_4MM_SMSC")
      (libsource (lib "eagle-import") (part "CP2104"))
    )
    (comp (ref "U5")
      (value "TPS7A0318PDQNR")
      (footprint "eagle-import:DQN0004A-MFG")
      (fields (field (name "COPYRIGHT") "Copyright (C) 2025 Ultra Librarian. All rights reserved."))
      (libsource (lib "eagle-import") (part "TPS7A0318PDQNR"))
    )
    (comp (ref "U6")
      (value "TPS7A0333PDQNR")
      (footprint "eagle-import:DQN0004A-MFG")
      (fields (field (name "COPYRIGHT") "Copyright (C) 2025 Ultra Librarian. All rights reserved."))
      (libsource (lib "eagle-import") (part "TPS7A0333PDQNR"))
    )
    (comp (ref "VBAT")
      (value "TEST-POINT3")
      (footprint "eagle-import:PAD.03X.03")
      (libsource (lib "eagle-import") (part "TEST-POINT3"))
    )
    (comp (ref "VBUS")
      (value "TEST-POINT3")
      (footprint "eagle-import:PAD.03X.03")
      (libsource (lib "eagle-import") (part "TEST-POINT3"))
    )
    (comp (ref "VDD")
      (value "TEST-POINT3")
      (footprint "eagle-import:PAD.03X.03")
      (libsource (lib "eagle-import") (part "TEST-POINT3"))
    )
    (comp (ref "VUSB")
      (value "TEST-POINT3")
      (footprint "eagle-import:PAD.03X.03")
      (libsource (lib "eagle-import") (part "TEST-POINT3"))
    )
    (comp (ref "Y1")
      (value "830065253")
      (footprint "eagle-import:830065253")
      (fields (field (name "MOUSER_PART_NUMBER") "710-830065253"))
      (libsource (lib "eagle-import") (part "830065253"))
    )
    (comp (ref "Y4")
      (value "ECS-320-10-48B-CKY-TR")
      (footprint "eagle-import:ECS3201048BCKYTR")
      (fields (field (name "MOUSER_PART_NUMBER") "520-S3201048BCKYTR"))
      (libsource (lib "eagle-import") (part "ECS-320-10-48B-CKY-TR"))
    )
  )
  (nets
    (net (code "1") (name "+3V3") (class "Default")
      (node (ref "3V3") (pin "P$1") (pinfunction "1_P$1") (pintype "bidirectional"))
      (node (ref "C28") (pin "1") (pinfunction "1_1") (pintype "passive"))
      (node (ref "C37") (pin "1") (pinfunction "1_1") (pintype "passive"))
      (node (ref "C39") (pin "2") (pinfunction "2_2") (pintype "passive"))
      (node (ref "IC1") (pin "B2") (pinfunction "VCCB_B2") (pintype "bidirectional"))
      (node (ref "IC5") (pin "3") (pinfunction "OUT2_3") (pintype "bidirectional"))
      (node (ref "JP36") (pin "2") (pinfunction "2_2") (pintype "passive"))
      (node (ref "JP8") (pin "8") (pinfunction "8_8") (pintype "passive"))
      (node (ref "Q2") (pin "1") (pinfunction "G_1") (pintype "bidirectional"))
      (node (ref "U2") (pin "2") (pinfunction "VDD_2") (pintype "bidirectional"))
      (node (ref "U6") (pin "1") (pinfunction "OUT_1") (pintype "power_in"))
    )
    (net (code "2") (name "/VIO") (class "Default")
      (node (ref "U3") (pin "5") (pinfunction "VIO_5") (pintype "power_in"))
    )
    (net (code "3") (name "1.8V") (class "Default")
      (node (ref "1V8") (pin "P$1") (pinfunction "1_P$1") (pintype "bidirectional"))
      (node (ref "C8") (pin "1") (pinfunction "1_1") (pintype "passive"))
      (node (ref "IC5") (pin "1") (pinfunction "OUT1_1") (pintype "bidirectional"))
      (node (ref "JP20") (pin "2") (pinfunction "2_2") (pintype "passive"))
      (node (ref "JP21") (pin "2") (pinfunction "2_2") (pintype "passive"))
      (node (ref "JP23") (pin "2") (pinfunction "2_2") (pintype "passive"))
      (node (ref "JP27") (pin "2") (pinfunction "2_2") (pintype "passive"))
      (node (ref "JP29") (pin "2") (pinfunction "2_2") (pintype "passive"))
      (node (ref "JP34") (pin "1") (pinfunction "1_1") (pintype "passive"))
      (node (ref "JP8") (pin "7") (pinfunction "7_7") (pintype "passive"))
      (node (ref "Q1") (pin "1") (pinfunction "G_1") (pintype "bidirectional"))
      (node (ref "U5") (pin "1") (pinfunction "OUT_1") (pintype "power_in"))
    )
    (net (code "4") (name "1V8_EN") (class "Default")
      (node (ref "1V8_EN") (pin "P$1") (pinfunction "1_P$1") (pintype "bidirectional"))
      (node (ref "IC13") (pin "G1") (pinfunction "P0.26_G1") (pintype "bidirectional"))
      (node (ref "IC5") (pin "6") (pinfunction "EN1_6") (pintype "bidirectional"))
      (node (ref "JP9") (pin "7") (pinfunction "7_7") (pintype "passive"))
      (node (ref "R16") (pin "2") (pinfunction "2_2") (pintype "passive"))
      (node (ref "R22") (pin "2") (pinfunction "2_2") (pintype "passive"))
      (node (ref "U5") (pin "3") (pinfunction "EN_3") (pintype "input"))
    )
    (net (code "5") (name "3V3_EN") (class "Default")
      (node (ref "3V3_EN") (pin "P$1") (pinfunction "1_P$1") (pintype "bidirectional"))
      (node (ref "IC13") (pin "H2") (pinfunction "P0.27_H2") (pintype "bidirectional"))
      (node (ref "IC5") (pin "4") (pinfunction "EN2_4") (pintype "bidirectional"))
      (node (ref "JP9") (pin "8") (pinfunction "8_8") (pintype "passive"))
      (node (ref "R21") (pin "2") (pinfunction "2_2") (pintype "passive"))
      (node (ref "R23") (pin "2") (pinfunction "2_2") (pintype "passive"))
      (node (ref "U6") (pin "3") (pinfunction "EN_3") (pintype "input"))
    )
    (net (code "6") (name "ANT") (class "Default")
      (node (ref "C15") (pin "1") (pinfunction "1_1") (pintype "passive"))
      (node (ref "IC13") (pin "H23") (pinfunction "ANT_H23") (pintype "bidirectional"))
    )
    (net (code "7") (name "BAT_ALRT") (class "Default")
      (node (ref "IC13") (pin "AC15") (pinfunction "P0.19_AC15") (pintype "bidirectional"))
      (node (ref "IC2") (pin "B4") (pinfunction "~{ALRT}_B4") (pintype "bidirectional"))
    )
    (net (code "8") (name "BMI_AINT") (class "Default")
      (node (ref "IC8") (pin "9") (pinfunction "INT2_9") (pintype "bidirectional"))
      (node (ref "JP6") (pin "1") (pinfunction "1_1") (pintype "passive"))
    )
    (net (code "9") (name "BMI_ASCL") (class "Default")
      (node (ref "IC8") (pin "3") (pinfunction "ASCX_3") (pintype "bidirectional"))
      (node (ref "JP5") (pin "2") (pinfunction "2_2") (pintype "passive"))
    )
    (net (code "10") (name "BMI_ASDA") (class "Default")
      (node (ref "IC8") (pin "2") (pinfunction "ASDX_2") (pintype "bidirectional"))
      (node (ref "JP3") (pin "2") (pinfunction "2_2") (pintype "passive"))
    )
    (net (code "11") (name "CHG+") (class "Default")
      (node (ref "C31") (pin "1") (pinfunction "1_1") (pintype "passive"))
      (node (ref "CHG+") (pin "P$1") (pinfunction "1_P$1") (pintype "bidirectional"))
      (node (ref "IC12") (pin "A2") (pinfunction "IN_A2") (pintype "bidirectional"))
      (node (ref "R11") (pin "2") (pinfunction "2_2") (pintype "passive"))
      (node (ref "S1") (pin "3") (pinfunction "S_3") (pintype "passive"))
      (node (ref "U$8") (pin "CHG+") (pinfunction "CHG+_CHG+") (pintype "bidirectional"))
    )
    (net (code "12") (name "CHG_DET") (class "Default")
      (node (ref "CHG_DET") (pin "P$1") (pinfunction "1_P$1") (pintype "bidirectional"))
      (node (ref "IC13") (pin "J1") (pinfunction "P0.04__AIN2_J1") (pintype "bidirectional"))
      (node (ref "R10") (pin "1") (pinfunction "1_1") (pintype "passive"))
      (node (ref "R11") (pin "1") (pinfunction "1_1") (pintype "passive"))
    )
    (net (code "13") (name "CS_IMU") (class "Default")
      (node (ref "CS_IMU") (pin "P$1") (pinfunction "1_P$1") (pintype "bidirectional"))
      (node (ref "IC13") (pin "B9") (pinfunction "P0.30__AIN6_B9") (pintype "bidirectional"))
      (node (ref "IC8") (pin "12") (pinfunction "CSB_12") (pintype "bidirectional"))
      (node (ref "JP9") (pin "5") (pinfunction "5_5") (pintype "passive"))
    )
    (net (code "14") (name "CS_NOR") (class "Default")
      (node (ref "CS_NOR") (pin "P$1") (pinfunction "1_P$1") (pintype "bidirectional"))
      (node (ref "IC13") (pin "B13") (pinfunction "P0.03__AIN1_B13") (pintype "bidirectional"))
      (node (ref "JP9") (pin "6") (pinfunction "6_6") (pintype "passive"))
      (node (ref "U$6") (pin "2") (pinfunction "DAT3_2") (pintype "bidirectional"))
    )
    (net (code "15") (name "DCC") (class "Default")
      (node (ref "IC13") (pin "B3") (pinfunction "DCC_B3") (pintype "bidirectional"))
      (node (ref "L3") (pin "1") (pinfunction "1_1") (pintype "passive"))
    )
    (net (code "16") (name "DCCH") (class "Default")
      (node (ref "IC13") (pin "AB2") (pinfunction "DCCH_AB2") (pintype "bidirectional"))
      (node (ref "L5") (pin "1") (pinfunction "1_1") (pintype "passive"))
    )
    (net (code "17") (name "DEC1") (class "Default")
      (node (ref "C33") (pin "2") (pinfunction "2_2") (pintype "passive"))
      (node (ref "IC13") (pin "C1") (pinfunction "DEC1_C1") (pintype "bidirectional"))
    )
    (net (code "18") (name "DEC2") (class "Default")
      (node (ref "C41") (pin "2") (pinfunction "2_2") (pintype "passive"))
      (node (ref "IC13") (pin "A18") (pinfunction "DEC2_1_A18") (pintype "bidirectional"))
    )
    (net (code "19") (name "DEC3") (class "Default")
      (node (ref "C38") (pin "2") (pinfunction "2_2") (pintype "passive"))
      (node (ref "IC13") (pin "D23") (pinfunction "DEC3_D23") (pintype "bidirectional"))
    )
    (net (code "20") (name "DEC46") (class "Default")
      (node (ref "C32") (pin "2") (pinfunction "2_2") (pintype "passive"))
      (node (ref "C42") (pin "2") (pinfunction "2_2") (pintype "passive"))
      (node (ref "C43") (pin "2") (pinfunction "2_2") (pintype "passive"))
      (node (ref "IC13") (pin "B5") (pinfunction "DEC4_B5") (pintype "bidirectional"))
      (node (ref "IC13") (pin "E24") (pinfunction "DEC2_2_E24") (pintype "bidirectional"))
      (node (ref "L4") (pin "1") (pinfunction "1_1") (pintype "passive"))
    )
    (net (code "21") (name "DEC_USB") (class "Default")
      (node (ref "C44") (pin "2") (pinfunction "2_2") (pintype "passive"))
      (node (ref "IC13") (pin "AC5") (pinfunction "DECUSB_AC5") (pintype "bidirectional"))
    )
    (net (code "22") (name "DTR") (class "Default")
      (node (ref "C22") (pin "2") (pinfunction "2_2") (pintype "passive"))
      (node (ref "U3") (pin "23") (pinfunction "DTR_23") (pintype "output"))
    )
    (net (code "23") (name "GBAT") (class "Default")
      (node (ref "C35") (pin "2") (pinfunction "2_2") (pintype "passive"))
      (node (ref "IC6") (pin "4") (pinfunction "VSS_4") (pintype "bidirectional"))
      (node (ref "IC9") (pin "4") (pinfunction "S2_4") (pintype "bidirectional"))
      (node (ref "JP11") (pin "2") (pinfunction "2_2") (pintype "passive"))
      (node (ref "U$3") (pin "BAT-") (pinfunction "BAT-_BAT-") (pintype "power_in"))
    )
    (net (code "24") (name "GND") (class "Default")
      (node (ref "C10") (pin "1") (pinfunction "1_1") (pintype "passive"))
      (node (ref "C11") (pin "1") (pinfunction "1_1") (pintype "passive"))
      (node (ref "C12") (pin "2") (pinfunction "2_2") (pintype "passive"))
      (node (ref "C13") (pin "1") (pinfunction "1_1") (pintype "passive"))
      (node (ref "C14") (pin "2") (pinfunction "2_2") (pintype "passive"))
      (node (ref "C17") (pin "1") (pinfunction "1_1") (pintype "passive"))
      (node (ref "C18") (pin "1") (pinfunction "1_1") (pintype "passive"))
      (node (ref "C19") (pin "2") (pinfunction "2_2") (pintype "passive"))
      (node (ref "C2") (pin "2") (pinfunction "2_2") (pintype "passive"))
      (node (ref "C20") (pin "2") (pinfunction "2_2") (pintype "passive"))
      (node (ref "C21") (pin "2") (pinfunction "2_2") (pintype "passive"))
      (node (ref "C23") (pin "1") (pinfunction "1_1") (pintype "passive"))
      (node (ref "C24") (pin "2") (pinfunction "2_2") (pintype "passive"))
      (node (ref "C25") (pin "2") (pinfunction "2_2") (pintype "passive"))
      (node (ref "C26") (pin "1") (pinfunction "1_1") (pintype "passive"))
      (node (ref "C27") (pin "1") (pinfunction "1_1") (pintype "passive"))
      (node (ref "C28") (pin "2") (pinfunction "2_2") (pintype "passive"))
      (node (ref "C3") (pin "2") (pinfunction "2_2") (pintype "passive"))
      (node (ref "C31") (pin "2") (pinfunction "2_2") (pintype "passive"))
      (node (ref "C32") (pin "1") (pinfunction "1_1") (pintype "passive"))
      (node (ref "C33") (pin "1") (pinfunction "1_1") (pintype "passive"))
      (node (ref "C34") (pin "1") (pinfunction "1_1") (pintype "passive"))
      (node (ref "C36") (pin "1") (pinfunction "1_1") (pintype "passive"))
      (node (ref "C37") (pin "2") (pinfunction "2_2") (pintype "passive"))
      (node (ref "C38") (pin "1") (pinfunction "1_1") (pintype "passive"))
      (node (ref "C39") (pin "1") (pinfunction "1_1") (pintype "passive"))
      (node (ref "C4") (pin "2") (pinfunction "2_2") (pintype "passive"))
      (node (ref "C40") (pin "2") (pinfunction "2_2") (pintype "passive"))
      (node (ref "C41") (pin "1") (pinfunction "1_1") (pintype "passive"))
      (node (ref "C42") (pin "1") (pinfunction "1_1") (pintype "passive"))
      (node (ref "C43") (pin "1") (pinfunction "1_1") (pintype "passive"))
      (node (ref "C44") (pin "1") (pinfunction "1_1") (pintype "passive"))
      (node (ref "C45") (pin "1") (pinfunction "1_1") (pintype "passive"))
      (node (ref "C46") (pin "1") (pinfunction "1_1") (pintype "passive"))
      (node (ref "C47") (pin "2") (pinfunction "2_2") (pintype "passive"))
      (node (ref "C6") (pin "1") (pinfunction "1_1") (pintype "passive"))
      (node (ref "C7") (pin "2") (pinfunction "2_2") (pintype "passive"))
      (node (ref "C8") (pin "2") (pinfunction "2_2") (pintype "passive"))
      (node (ref "C9") (pin "1") (pinfunction "1_1") (pintype "passive"))
      (node (ref "GND") (pin "P$1") (pinfunction "1_P$1") (pintype "bidirectional"))
      (node (ref "IC1") (pin "B1") (pinfunction "GND_B1") (pintype "bidirectional"))
      (node (ref "IC10") (pin "B1") (pinfunction "GND_B1") (pintype "bidirectional"))
      (node (ref "IC10") (pin "B2") (pinfunction "ADSEL_B2") (pintype "bidirectional"))
      (node (ref "IC10") (pin "C3") (pinfunction "BYPASS_C3") (pintype "bidirectional"))
      (node (ref "IC12") (pin "D2") (pinfunction "GND_D2") (pintype "bidirectional"))
      (node (ref "IC13") (pin "B7") (pinfunction "VSS_1_B7") (pintype "bidirectional"))
      (node (ref "IC13") (pin "DP1") (pinfunction "VSS_2_DP1") (pintype "bidirectional"))
      (node (ref "IC13") (pin "F23") (pinfunction "VSS_P_F23") (pintype "bidirectional"))
      (node (ref "IC2") (pin "A1") (pinfunction "CTG_A1") (pintype "bidirectional"))
      (node (ref "IC2") (pin "A4") (pinfunction "GND_A4") (pintype "bidirectional"))
      (node (ref "IC2") (pin "B3") (pinfunction "QSTRT_B3") (pintype "bidirectional"))
      (node (ref "IC5") (pin "5") (pinfunction "GND_1_5") (pintype "bidirectional"))
      (node (ref "IC5") (pin "7") (pinfunction "GND_2_7") (pintype "bidirectional"))
      (node (ref "IC8") (pin "6") (pinfunction "GNDIO_6") (pintype "bidirectional"))
      (node (ref "IC8") (pin "7") (pinfunction "GND_7") (pintype "bidirectional"))
      (node (ref "IC9") (pin "1") (pinfunction "S1_1") (pintype "bidirectional"))
      (node (ref "J1") (pin "A1/B12") (pinfunction "GND_A1/B12") (pintype "power_in"))
      (node (ref "J1") (pin "B1/A12") (pinfunction "GND_B1/A12") (pintype "power_in"))
      (node (ref "J1") (pin "S1") (pinfunction "GND_S1") (pintype "power_in"))
      (node (ref "J1") (pin "S2") (pinfunction "GND_S2") (pintype "power_in"))
      (node (ref "J1") (pin "S3") (pinfunction "GND_S3") (pintype "power_in"))
      (node (ref "J1") (pin "S4") (pinfunction "GND_S4") (pintype "power_in"))
      (node (ref "J2") (pin "A1/B12") (pinfunction "GND_A1/B12") (pintype "power_in"))
      (node (ref "J2") (pin "B1/A12") (pinfunction "GND_B1/A12") (pintype "power_in"))
      (node (ref "J2") (pin "S1") (pinfunction "GND_S1") (pintype "power_in"))
      (node (ref "J2") (pin "S2") (pinfunction "GND_S2") (pintype "power_in"))
      (node (ref "J2") (pin "S3") (pinfunction "GND_S3") (pintype "power_in"))
      (node (ref "J2") (pin "S4") (pinfunction "GND_S4") (pintype "power_in"))
      (node (ref "JP1") (pin "1") (pinfunction "1_1") (pintype "passive"))
      (node (ref "JP11") (pin "1") (pinfunction "1_1") (pintype "passive"))
      (node (ref "L2") (pin "2") (pinfunction "2_2") (pintype "passive"))
      (node (ref "LED5") (pin "C") (pinfunction "C_C") (pintype "passive"))
      (node (ref "Q1") (pin "2") (pinfunction "S_2") (pintype "bidirectional"))
      (node (ref "Q2") (pin "2") (pinfunction "S_2") (pintype "bidirectional"))
      (node (ref "Q3") (pin "2") (pinfunction "S_2") (pintype "bidirectional"))
      (node (ref "Q4") (pin "2") (pinfunction "S_2") (pintype "bidirectional"))
      (node (ref "R10") (pin "2") (pinfunction "2_2") (pintype "passive"))
      (node (ref "R12") (pin "1") (pinfunction "1_1") (pintype "passive"))
      (node (ref "R16") (pin "1") (pinfunction "1_1") (pintype "passive"))
      (node (ref "R21") (pin "1") (pinfunction "1_1") (pintype "passive"))
      (node (ref "R22") (pin "1") (pinfunction "1_1") (pintype "passive"))
      (node (ref "R23") (pin "1") (pinfunction "1_1") (pintype "passive"))
      (node (ref "R4") (pin "2") (pinfunction "2_2") (pintype "passive"))
      (node (ref "R5") (pin "2") (pinfunction "2_2") (pintype "passive"))
      (node (ref "R6") (pin "2") (pinfunction "2_2") (pintype "passive"))
      (node (ref "R9") (pin "2") (pinfunction "2_2") (pintype "passive"))
      (node (ref "SW1") (pin "B") (pinfunction "S_B") (pintype "passive"))
      (node (ref "SW1") (pin "B'") (pinfunction "S1_B'") (pintype "passive"))
      (node (ref "U$8") (pin "CHG-") (pinfunction "CHG-_CHG-") (pintype "bidirectional"))
      (node (ref "U$8") (pin "CHG-1") (pinfunction "CHG-_CHG-1") (pintype "bidirectional"))
      (node (ref "U$8") (pin "CHG-2") (pinfunction "CHG-_CHG-2") (pintype "bidirectional"))
      (node (ref "U$8") (pin "CHG-3") (pinfunction "CHG-_CHG-3") (pintype "bidirectional"))
      (node (ref "U1") (pin "12") (pinfunction "GND_12") (pintype "bidirectional"))
      (node (ref "U1") (pin "4") (pinfunction "PGND_4") (pintype "bidirectional"))
      (node (ref "U2") (pin "3") (pinfunction "GND_3") (pintype "bidirectional"))
      (node (ref "U2") (pin "5") (pinfunction "ADDR_5") (pintype "bidirectional"))
      (node (ref "U2") (pin "6") (pinfunction "EP_6") (pintype "bidirectional"))
      (node (ref "U3") (pin "2") (pinfunction "GND_2") (pintype "power_in"))
      (node (ref "U5") (pin "2") (pinfunction "GND_2") (pintype "power_in"))
      (node (ref "U5") (pin "5") (pinfunction "THERMAL_PAD_5") (pintype "passive"))
      (node (ref "U6") (pin "2") (pinfunction "GND_2") (pintype "power_in"))
      (node (ref "U6") (pin "5") (pinfunction "THERMAL_PAD_5") (pintype "passive"))
      (node (ref "Y4") (pin "2") (pinfunction "GND_&_LID_2") (pintype "bidirectional"))
    )
    (net (code "25") (name "INT_BMM") (class "Default")
      (node (ref "IC13") (pin "J24") (pinfunction "P0.10__NFC2_J24") (pintype "bidirectional"))
      (node (ref "JP7") (pin "1") (pinfunction "1_1") (pintype "passive"))
    )
    (net (code "26") (name "INT_IMU") (class "Default")
      (node (ref "IC13") (pin "B11") (pinfunction "P0.28__AIN4_B11") (pintype "bidirectional"))
      (node (ref "IC8") (pin "4") (pinfunction "INT1_4") (pintype "bidirectional"))
      (node (ref "INT_IMU") (pin "P$1") (pinfunction "1_P$1") (pintype "bidirectional"))
      (node (ref "JP9") (pin "1") (pinfunction "1_1") (pintype "passive"))
    )
    (net (code "27") (name "INT_PMIC") (class "Default")
      (node (ref "IC12") (pin "A1") (pinfunction "~{INT}_A1") (pintype "bidirectional"))
      (node (ref "IC13") (pin "AD18") (pinfunction "P0.22_AD18") (pintype "bidirectional"))
      (node (ref "INT_PMIC") (pin "P$1") (pinfunction "1_P$1") (pintype "bidirectional"))
      (node (ref "JP9") (pin "2") (pinfunction "2_2") (pintype "passive"))
    )
    (net (code "28") (name "INT_PPG") (class "Default")
      (node (ref "IC13") (pin "M2") (pinfunction "P0.07_M2") (pintype "bidirectional"))
      (node (ref "INT_PPG") (pin "P$1") (pinfunction "1_P$1") (pintype "bidirectional"))
      (node (ref "JP19") (pin "2") (pinfunction "2_2") (pintype "passive"))
      (node (ref "JP9") (pin "3") (pinfunction "3_3") (pintype "passive"))
    )
    (net (code "29") (name "MAX_MFIO") (class "Default")
      (node (ref "IC13") (pin "N1") (pinfunction "P0.08_N1") (pintype "bidirectional"))
      (node (ref "MAX_MFIO") (pin "P$1") (pinfunction "1_P$1") (pintype "bidirectional"))
    )
    (net (code "30") (name "MAX_RST") (class "Default")
      (node (ref "IC13") (pin "K2") (pinfunction "P0.05_K2") (pintype "bidirectional"))
      (node (ref "MAX_RST") (pin "P$1") (pinfunction "1_P$1") (pintype "bidirectional"))
    )
    (net (code "31") (name "MISO") (class "Default")
      (node (ref "IC13") (pin "AD10") (pinfunction "P0.15_AD10") (pintype "bidirectional"))
      (node (ref "IC8") (pin "1") (pinfunction "SDO_1") (pintype "bidirectional"))
      (node (ref "JP8") (pin "4") (pinfunction "4_4") (pintype "passive"))
      (node (ref "MISO") (pin "P$1") (pinfunction "1_P$1") (pintype "bidirectional"))
      (node (ref "U$6") (pin "6") (pinfunction "DAT0_6") (pintype "input"))
    )
    (net (code "32") (name "MOSI") (class "Default")
      (node (ref "IC13") (pin "AD8") (pinfunction "P0.13_AD8") (pintype "bidirectional"))
      (node (ref "IC8") (pin "14") (pinfunction "SDX_14") (pintype "bidirectional"))
      (node (ref "JP8") (pin "3") (pinfunction "3_3") (pintype "passive"))
      (node (ref "MOSI") (pin "P$1") (pinfunction "1_P$1") (pintype "bidirectional"))
      (node (ref "U$6") (pin "5") (pinfunction "CMD_5") (pintype "bidirectional"))
    )
    (net (code "33") (name "N$18") (class "Default")
      (node (ref "IC10") (pin "A1") (pinfunction "INT_A1") (pintype "bidirectional"))
      (node (ref "INT_BMM") (pin "P$1") (pinfunction "1_P$1") (pintype "bidirectional"))
      (node (ref "JP6") (pin "2") (pinfunction "2_2") (pintype "passive"))
      (node (ref "JP7") (pin "2") (pinfunction "2_2") (pintype "passive"))
      (node (ref "JP9") (pin "4") (pinfunction "4_4") (pintype "passive"))
    )
    (net (code "34") (name "NUSB_DN") (class "Default")
      (node (ref "IC13") (pin "AD4") (pinfunction "D-_AD4") (pintype "bidirectional"))
      (node (ref "J2") (pin "A7") (pinfunction "DN1_A7") (pintype "bidirectional"))
      (node (ref "J2") (pin "B7") (pinfunction "DN2_B7") (pintype "bidirectional"))
    )
    (net (code "35") (name "NUSB_DP") (class "Default")
      (node (ref "IC13") (pin "AD6") (pinfunction "D+_AD6") (pintype "bidirectional"))
      (node (ref "J2") (pin "A6") (pinfunction "DP1_A6") (pintype "bidirectional"))
      (node (ref "J2") (pin "B6") (pinfunction "DP2_B6") (pintype "bidirectional"))
    )
    (net (code "36") (name "NVUSB") (class "Default")
      (node (ref "C34") (pin "2") (pinfunction "2_2") (pintype "passive"))
      (node (ref "IC13") (pin "AD2") (pinfunction "VBUS_AD2") (pintype "bidirectional"))
      (node (ref "J2") (pin "A4/B9") (pinfunction "VBUS_A4/B9") (pintype "power_in"))
      (node (ref "J2") (pin "B4/A9") (pinfunction "VBUS_B4/A9") (pintype "power_in"))
      (node (ref "JP12") (pin "1") (pinfunction "1_1") (pintype "passive"))
      (node (ref "JP13") (pin "2") (pinfunction "2_2") (pintype "passive"))
      (node (ref "S1") (pin "1") (pinfunction "O_1") (pintype "passive"))
      (node (ref "S1") (pin "2") (pinfunction "P_2") (pintype "passive"))
      (node (ref "VUSB") (pin "P$1") (pinfunction "1_P$1") (pintype "bidirectional"))
    )
    (net (code "37") (name "Net-(C15-Pad2)") (class "Default")
      (node (ref "C15") (pin "2") (pinfunction "2_2") (pintype "passive"))
      (node (ref "L1") (pin "2") (pinfunction "2_2") (pintype "passive"))
      (node (ref "L2") (pin "1") (pinfunction "1_1") (pintype "passive"))
    )
    (net (code "38") (name "Net-(E1-FEED)") (class "Default")
      (node (ref "E1") (pin "1") (pinfunction "FEED_1") (pintype "input"))
      (node (ref "L1") (pin "1") (pinfunction "1_1") (pintype "passive"))
    )
    (net (code "39") (name "Net-(IC1-B1)") (class "Default")
      (node (ref "IC1") (pin "A2") (pinfunction "B1_A2") (pintype "bidirectional"))
      (node (ref "U2") (pin "1") (pinfunction "SDA_1") (pintype "bidirectional"))
    )
    (net (code "40") (name "Net-(IC1-B2)") (class "Default")
      (node (ref "IC1") (pin "A1") (pinfunction "B2_A1") (pintype "bidirectional"))
      (node (ref "U2") (pin "4") (pinfunction "SCL_4") (pintype "bidirectional"))
    )
    (net (code "41") (name "Net-(IC1-OE)") (class "Default")
      (node (ref "C40") (pin "1") (pinfunction "1_1") (pintype "passive"))
      (node (ref "IC1") (pin "C1") (pinfunction "VCCA_C1") (pintype "bidirectional"))
      (node (ref "IC1") (pin "C2") (pinfunction "OE_C2") (pintype "bidirectional"))
      (node (ref "JP29") (pin "1") (pinfunction "1_1") (pintype "passive"))
      (node (ref "JP30") (pin "1") (pinfunction "1_1") (pintype "passive"))
    )
    (net (code "42") (name "Net-(IC6-BAT)") (class "Default")
      (node (ref "C35") (pin "1") (pinfunction "1_1") (pintype "passive"))
      (node (ref "IC6") (pin "5") (pinfunction "BAT_5") (pintype "bidirectional"))
      (node (ref "R13") (pin "2") (pinfunction "2_2") (pintype "passive"))
    )
    (net (code "43") (name "Net-(IC6-COUT)") (class "Default")
      (node (ref "IC6") (pin "2") (pinfunction "COUT_2") (pintype "bidirectional"))
      (node (ref "IC9") (pin "2") (pinfunction "G1_2") (pintype "bidirectional"))
    )
    (net (code "44") (name "Net-(IC6-DOUT)") (class "Default")
      (node (ref "IC6") (pin "3") (pinfunction "DOUT_3") (pintype "bidirectional"))
      (node (ref "IC9") (pin "5") (pinfunction "G2_5") (pintype "bidirectional"))
    )
    (net (code "45") (name "Net-(IC6-V-)") (class "Default")
      (node (ref "IC6") (pin "6") (pinfunction "V-_6") (pintype "bidirectional"))
      (node (ref "R12") (pin "2") (pinfunction "2_2") (pintype "passive"))
    )
    (net (code "46") (name "Net-(IC8-VDD)") (class "Default")
      (node (ref "C17") (pin "2") (pinfunction "2_2") (pintype "passive"))
      (node (ref "C18") (pin "2") (pinfunction "2_2") (pintype "passive"))
      (node (ref "C27") (pin "2") (pinfunction "2_2") (pintype "passive"))
      (node (ref "IC8") (pin "5") (pinfunction "VDDIO_5") (pintype "bidirectional"))
      (node (ref "IC8") (pin "8") (pinfunction "VDD_8") (pintype "bidirectional"))
      (node (ref "JP23") (pin "1") (pinfunction "1_1") (pintype "passive"))
      (node (ref "JP24") (pin "1") (pinfunction "1_1") (pintype "passive"))
    )
    (net (code "47") (name "Net-(IC9-D1_1)") (class "Default")
      (node (ref "IC9") (pin "3") (pinfunction "D2_1_3") (pintype "bidirectional"))
      (node (ref "IC9") (pin "6") (pinfunction "D1_1_6") (pintype "bidirectional"))
      (node (ref "IC9") (pin "7") (pinfunction "D1_2_7") (pintype "bidirectional"))
      (node (ref "IC9") (pin "8") (pinfunction "D2_2_8") (pintype "bidirectional"))
    )
    (net (code "48") (name "Net-(IC10-CRST)") (class "Default")
      (node (ref "C23") (pin "2") (pinfunction "2_2") (pintype "passive"))
      (node (ref "IC10") (pin "C2") (pinfunction "CRST_C2") (pintype "bidirectional"))
    )
    (net (code "49") (name "Net-(IC10-SCK)") (class "Default")
      (node (ref "IC10") (pin "A3") (pinfunction "SCK_A3") (pintype "bidirectional"))
      (node (ref "JP4") (pin "1") (pinfunction "1_1") (pintype "passive"))
      (node (ref "JP5") (pin "1") (pinfunction "1_1") (pintype "passive"))
    )
    (net (code "50") (name "Net-(IC10-SDA)") (class "Default")
      (node (ref "IC10") (pin "A2") (pinfunction "SDA_A2") (pintype "bidirectional"))
      (node (ref "JP2") (pin "1") (pinfunction "1_1") (pintype "passive"))
      (node (ref "JP3") (pin "1") (pinfunction "1_1") (pintype "passive"))
    )
    (net (code "51") (name "Net-(IC10-VDD)") (class "Default")
      (node (ref "C26") (pin "2") (pinfunction "2_2") (pintype "passive"))
      (node (ref "IC10") (pin "B3") (pinfunction "VDDIO_B3") (pintype "bidirectional"))
      (node (ref "IC10") (pin "C1") (pinfunction "VDD_C1") (pintype "bidirectional"))
      (node (ref "JP21") (pin "1") (pinfunction "1_1") (pintype "passive"))
      (node (ref "JP22") (pin "1") (pinfunction "1_1") (pintype "passive"))
    )
    (net (code "52") (name "Net-(IC13-P0.24)") (class "Default")
      (node (ref "IC13") (pin "AD20") (pinfunction "P0.24_AD20") (pintype "bidirectional"))
      (node (ref "R14") (pin "2") (pinfunction "2_2") (pintype "passive"))
    )
    (net (code "53") (name "Net-(IC13-P0.25)") (class "Default")
      (node (ref "IC13") (pin "AC21") (pinfunction "P0.25_AC21") (pintype "bidirectional"))
      (node (ref "R15") (pin "2") (pinfunction "2_2") (pintype "passive"))
    )
    (net (code "54") (name "Net-(J1-CC1)") (class "Default")
      (node (ref "J1") (pin "A5") (pinfunction "CC1_A5") (pintype "bidirectional"))
      (node (ref "R4") (pin "1") (pinfunction "1_1") (pintype "passive"))
    )
    (net (code "55") (name "Net-(J1-CC2)") (class "Default")
      (node (ref "J1") (pin "B5") (pinfunction "CC2_B5") (pintype "bidirectional"))
      (node (ref "R5") (pin "1") (pinfunction "1_1") (pintype "passive"))
    )
    (net (code "56") (name "Net-(J2-CC1)") (class "Default")
      (node (ref "J2") (pin "A5") (pinfunction "CC1_A5") (pintype "bidirectional"))
      (node (ref "R6") (pin "1") (pinfunction "1_1") (pintype "passive"))
    )
    (net (code "57") (name "Net-(J2-CC2)") (class "Default")
      (node (ref "J2") (pin "B5") (pinfunction "CC2_B5") (pintype "bidirectional"))
      (node (ref "R9") (pin "1") (pinfunction "1_1") (pintype "passive"))
    )
    (net (code "58") (name "Net-(JP10-Pad1)") (class "Default")
      (node (ref "JP10") (pin "1") (pinfunction "1_1") (pintype "passive"))
      (node (ref "R1") (pin "1") (pinfunction "1_1") (pintype "passive"))
      (node (ref "R19") (pin "1") (pinfunction "1_1") (pintype "passive"))
      (node (ref "R20") (pin "1") (pinfunction "1_1") (pintype "passive"))
      (node (ref "R24") (pin "1") (pinfunction "1_1") (pintype "passive"))
      (node (ref "R27") (pin "1") (pinfunction "1_1") (pintype "passive"))
    )
    (net (code "59") (name "Net-(L3-Pad2)") (class "Default")
      (node (ref "L3") (pin "2") (pinfunction "2_2") (pintype "passive"))
      (node (ref "L4") (pin "2") (pinfunction "2_2") (pintype "passive"))
    )
    (net (code "60") (name "Net-(LED1-PadA)") (class "Default")
      (node (ref "LED1") (pin "A") (pinfunction "A_A") (pintype "passive"))
      (node (ref "R1") (pin "2") (pinfunction "2_2") (pintype "passive"))
    )
    (net (code "61") (name "Net-(LED2-PadA)") (class "Default")
      (node (ref "LED2") (pin "A") (pinfunction "A_A") (pintype "passive"))
      (node (ref "R19") (pin "2") (pinfunction "2_2") (pintype "passive"))
    )
    (net (code "62") (name "Net-(LED3-PadA)") (class "Default")
      (node (ref "LED3") (pin "A") (pinfunction "A_A") (pintype "passive"))
      (node (ref "R2") (pin "1") (pinfunction "1_1") (pintype "passive"))
    )
    (net (code "63") (name "Net-(LED4-PadA)") (class "Default")
      (node (ref "LED4") (pin "A") (pinfunction "A_A") (pintype "passive"))
      (node (ref "R3") (pin "1") (pinfunction "1_1") (pintype "passive"))
    )
    (net (code "64") (name "Net-(LED5-PadA)") (class "Default")
      (node (ref "LED5") (pin "A") (pinfunction "A_A") (pintype "passive"))
      (node (ref "R20") (pin "2") (pinfunction "2_2") (pintype "passive"))
    )
    (net (code "65") (name "Net-(LED6-PadA)") (class "Default")
      (node (ref "LED6") (pin "A") (pinfunction "A_A") (pintype "passive"))
      (node (ref "R24") (pin "2") (pinfunction "2_2") (pintype "passive"))
    )
    (net (code "66") (name "Net-(LED7-PadA)") (class "Default")
      (node (ref "LED7") (pin "A") (pinfunction "A_A") (pintype "passive"))
      (node (ref "R27") (pin "2") (pinfunction "2_2") (pintype "passive"))
    )
    (net (code "67") (name "Net-(Q1-D)") (class "Default")
      (node (ref "LED1") (pin "C") (pinfunction "C_C") (pintype "passive"))
      (node (ref "Q1") (pin "3") (pinfunction "D_3") (pintype "bidirectional"))
    )
    (net (code "68") (name "Net-(Q2-D)") (class "Default")
      (node (ref "LED2") (pin "C") (pinfunction "C_C") (pintype "passive"))
      (node (ref "Q2") (pin "3") (pinfunction "D_3") (pintype "bidirectional"))
    )
    (net (code "69") (name "Net-(Q3-D)") (class "Default")
      (node (ref "LED6") (pin "C") (pinfunction "C_C") (pintype "passive"))
      (node (ref "Q3") (pin "3") (pinfunction "D_3") (pintype "bidirectional"))
    )
    (net (code "70") (name "Net-(Q4-D)") (class "Default")
      (node (ref "LED7") (pin "C") (pinfunction "C_C") (pintype "passive"))
      (node (ref "Q4") (pin "3") (pinfunction "D_3") (pintype "bidirectional"))
    )
    (net (code "71") (name "Net-(U$6-VDD)") (class "Default")
      (node (ref "JP20") (pin "1") (pinfunction "1_1") (pintype "passive"))
      (node (ref "JP36") (pin "1") (pinfunction "1_1") (pintype "passive"))
      (node (ref "U$6") (pin "8") (pinfunction "VDD_8") (pintype "power_in"))
    )
    (net (code "72") (name "Net-(U$6-VSS)") (class "Default")
      (node (ref "C47") (pin "1") (pinfunction "1_1") (pintype "passive"))
      (node (ref "U$6") (pin "4") (pinfunction "VSS_4") (pintype "power_in"))
    )
    (net (code "73") (name "Net-(U1-INT)") (class "Default")
      (node (ref "JP19") (pin "1") (pinfunction "1_1") (pintype "passive"))
      (node (ref "U1") (pin "13") (pinfunction "INT_13") (pintype "bidirectional"))
    )
    (net (code "74") (name "Net-(U1-SCL)") (class "Default")
      (node (ref "JP15") (pin "1") (pinfunction "1_1") (pintype "passive"))
      (node (ref "U1") (pin "2") (pinfunction "SCL_2") (pintype "bidirectional"))
    )
    (net (code "75") (name "Net-(U1-SDA)") (class "Default")
      (node (ref "JP16") (pin "1") (pinfunction "1_1") (pintype "passive"))
      (node (ref "U1") (pin "3") (pinfunction "SDA_3") (pintype "bidirectional"))
    )
    (net (code "76") (name "Net-(U1-VDD)") (class "Default")
      (node (ref "C4") (pin "1") (pinfunction "1_1") (pintype "passive"))
      (node (ref "JP27") (pin "1") (pinfunction "1_1") (pintype "passive"))
      (node (ref "JP28") (pin "1") (pinfunction "1_1") (pintype "passive"))
      (node (ref "U1") (pin "11") (pinfunction "VDD_11") (pintype "bidirectional"))
    )
    (net (code "77") (name "Net-(U3A-#RST)") (class "Default")
      (node (ref "R18") (pin "1") (pinfunction "1_1") (pintype "passive"))
      (node (ref "U3") (pin "9") (pinfunction "#RST_9") (pintype "bidirectional"))
    )
    (net (code "78") (name "Net-(U3A-GPIO0{slash}TXLED)") (class "Default")
      (node (ref "LED3") (pin "C") (pinfunction "C_C") (pintype "passive"))
      (node (ref "U3") (pin "14") (pinfunction "GPIO0/TXLED_14") (pintype "bidirectional"))
    )
    (net (code "79") (name "Net-(U3A-GPIO1{slash}RXLED)") (class "Default")
      (node (ref "LED4") (pin "C") (pinfunction "C_C") (pintype "passive"))
      (node (ref "U3") (pin "13") (pinfunction "GPIO1/RXLED_13") (pintype "bidirectional"))
    )
    (net (code "80") (name "Net-(U3A-VDD)") (class "Default")
      (node (ref "C14") (pin "1") (pinfunction "1_1") (pintype "passive"))
      (node (ref "R18") (pin "2") (pinfunction "2_2") (pintype "passive"))
      (node (ref "R2") (pin "2") (pinfunction "2_2") (pintype "passive"))
      (node (ref "R3") (pin "2") (pinfunction "2_2") (pintype "passive"))
      (node (ref "U3") (pin "6") (pinfunction "VDD_6") (pintype "power_in"))
    )
    (net (code "81") (name "Net-(U3A-VPP)") (class "Default")
      (node (ref "C7") (pin "1") (pinfunction "1_1") (pintype "passive"))
      (node (ref "U3") (pin "16") (pinfunction "VPP_16") (pintype "bidirectional"))
    )
    (net (code "82") (name "RESET") (class "Default")
      (node (ref "C22") (pin "1") (pinfunction "1_1") (pintype "passive"))
      (node (ref "D4") (pin "A") (pinfunction "A_A") (pintype "passive"))
      (node (ref "IC13") (pin "AC13") (pinfunction "P0.18__NRESET_AC13") (pintype "bidirectional"))
      (node (ref "JP1") (pin "7") (pinfunction "7_7") (pintype "passive"))
      (node (ref "NRST") (pin "P$1") (pinfunction "1_P$1") (pintype "bidirectional"))
      (node (ref "R7") (pin "2") (pinfunction "2_2") (pintype "passive"))
      (node (ref "SW1") (pin "A") (pinfunction "P_A") (pintype "passive"))
      (node (ref "SW1") (pin "A'") (pinfunction "P1_A'") (pintype "passive"))
    )
    (net (code "83") (name "RX") (class "Default")
      (node (ref "JP1") (pin "5") (pinfunction "5_5") (pintype "passive"))
      (node (ref "R14") (pin "1") (pinfunction "1_1") (pintype "passive"))
      (node (ref "RX") (pin "P$1") (pinfunction "1_P$1") (pintype "bidirectional"))
      (node (ref "U3") (pin "21") (pinfunction "TXD_21") (pintype "output"))
    )
    (net (code "84") (name "SCK") (class "Default")
      (node (ref "IC13") (pin "AC9") (pinfunction "P0.14_AC9") (pintype "bidirectional"))
      (node (ref "IC8") (pin "13") (pinfunction "SCX_13") (pintype "bidirectional"))
      (node (ref "JP8") (pin "5") (pinfunction "5_5") (pintype "passive"))
      (node (ref "SCK") (pin "P$1") (pinfunction "1_P$1") (pintype "bidirectional"))
      (node (ref "U$6") (pin "3") (pinfunction "CLK_3") (pintype "bidirectional"))
    )
    (net (code "85") (name "SCL") (class "Default")
      (node (ref "IC1") (pin "D1") (pinfunction "A2_D1") (pintype "bidirectional"))
      (node (ref "IC12") (pin "B1") (pinfunction "SCL_B1") (pintype "bidirectional"))
      (node (ref "IC13") (pin "T2") (pinfunction "P0.11_T2") (pintype "bidirectional"))
      (node (ref "IC2") (pin "B2") (pinfunction "SCL_B2") (pintype "bidirectional"))
      (node (ref "JP15") (pin "2") (pinfunction "2_2") (pintype "passive"))
      (node (ref "JP4") (pin "2") (pinfunction "2_2") (pintype "passive"))
      (node (ref "JP8") (pin "2") (pinfunction "2_2") (pintype "passive"))
      (node (ref "R8") (pin "2") (pinfunction "2_2") (pintype "passive"))
      (node (ref "SCL") (pin "P$1") (pinfunction "1_P$1") (pintype "bidirectional"))
    )
    (net (code "86") (name "SDA") (class "Default")
      (node (ref "IC1") (pin "D2") (pinfunction "A1_D2") (pintype "bidirectional"))
      (node (ref "IC12") (pin "C1") (pinfunction "SDA_C1") (pintype "bidirectional"))
      (node (ref "IC13") (pin "U1") (pinfunction "P0.12_U1") (pintype "bidirectional"))
      (node (ref "IC2") (pin "B1") (pinfunction "SDA_B1") (pintype "bidirectional"))
      (node (ref "JP16") (pin "2") (pinfunction "2_2") (pintype "passive"))
      (node (ref "JP2") (pin "2") (pinfunction "2_2") (pintype "passive"))
      (node (ref "JP8") (pin "1") (pinfunction "1_1") (pintype "passive"))
      (node (ref "R17") (pin "2") (pinfunction "2_2") (pintype "passive"))
      (node (ref "SDA") (pin "P$1") (pinfunction "1_P$1") (pintype "bidirectional"))
    )
    (net (code "87") (name "SWCLK") (class "Default")
      (node (ref "IC13") (pin "AA24") (pinfunction "SWDCLK_AA24") (pintype "bidirectional"))
      (node (ref "JP1") (pin "4") (pinfunction "4_4") (pintype "passive"))
      (node (ref "SWCLK") (pin "P$1") (pinfunction "1_P$1") (pintype "bidirectional"))
    )
    (net (code "88") (name "SWDIO") (class "Default")
      (node (ref "IC13") (pin "AC24") (pinfunction "SWDIO_AC24") (pintype "bidirectional"))
      (node (ref "JP1") (pin "3") (pinfunction "3_3") (pintype "passive"))
      (node (ref "SWDIO") (pin "P$1") (pinfunction "1_P$1") (pintype "bidirectional"))
    )
    (net (code "89") (name "SYS_LED") (class "Default")
      (node (ref "IC13") (pin "L1") (pinfunction "P0.06_L1") (pintype "bidirectional"))
      (node (ref "Q4") (pin "1") (pinfunction "G_1") (pintype "bidirectional"))
    )
    (net (code "90") (name "TX") (class "Default")
      (node (ref "JP1") (pin "6") (pinfunction "6_6") (pintype "passive"))
      (node (ref "R15") (pin "1") (pinfunction "1_1") (pintype "passive"))
      (node (ref "TX") (pin "P$1") (pinfunction "1_P$1") (pintype "bidirectional"))
      (node (ref "U3") (pin "20") (pinfunction "RXD_20") (pintype "input"))
    )
    (net (code "91") (name "USB_DN") (class "Default")
      (node (ref "J1") (pin "A7") (pinfunction "DN1_A7") (pintype "bidirectional"))
      (node (ref "J1") (pin "B7") (pinfunction "DN2_B7") (pintype "bidirectional"))
      (node (ref "U3") (pin "4") (pinfunction "D-_4") (pintype "bidirectional"))
    )
    (net (code "92") (name "USB_DP") (class "Default")
      (node (ref "J1") (pin "A6") (pinfunction "DP1_A6") (pintype "bidirectional"))
      (node (ref "J1") (pin "B6") (pinfunction "DP2_B6") (pintype "bidirectional"))
      (node (ref "U3") (pin "3") (pinfunction "D+_3") (pintype "bidirectional"))
    )
    (net (code "93") (name "VBAT") (class "Default")
      (node (ref "C2") (pin "1") (pinfunction "1_1") (pintype "passive"))
      (node (ref "IC12") (pin "C2") (pinfunction "BAT_C2") (pintype "bidirectional"))
      (node (ref "IC2") (pin "A2") (pinfunction "CELL_A2") (pintype "bidirectional"))
      (node (ref "IC2") (pin "A3") (pinfunction "VDD_A3") (pintype "bidirectional"))
      (node (ref "IC5") (pin "2") (pinfunction "IN_2") (pintype "bidirectional"))
      (node (ref "JP1") (pin "8") (pinfunction "8_8") (pintype "passive"))
      (node (ref "JP13") (pin "1") (pinfunction "1_1") (pintype "passive"))
      (node (ref "R13") (pin "1") (pinfunction "1_1") (pintype "passive"))
      (node (ref "U$3") (pin "BAT+") (pinfunction "BAT+_BAT+") (pintype "power_in"))
      (node (ref "VBAT") (pin "P$1") (pinfunction "1_P$1") (pintype "bidirectional"))
    )
    (net (code "94") (name "VBUS") (class "Default")
      (node (ref "C24") (pin "1") (pinfunction "1_1") (pintype "passive"))
      (node (ref "C25") (pin "1") (pinfunction "1_1") (pintype "passive"))
      (node (ref "C3") (pin "1") (pinfunction "1_1") (pintype "passive"))
      (node (ref "C36") (pin "2") (pinfunction "2_2") (pintype "passive"))
      (node (ref "IC12") (pin "B2") (pinfunction "SYS_B2") (pintype "bidirectional"))
      (node (ref "JP1") (pin "2") (pinfunction "2_2") (pintype "passive"))
      (node (ref "JP10") (pin "2") (pinfunction "2_2") (pintype "passive"))
      (node (ref "JP33") (pin "1") (pinfunction "1_1") (pintype "passive"))
      (node (ref "U1") (pin "10") (pinfunction "VLED+_10") (pintype "bidirectional"))
      (node (ref "U1") (pin "9") (pinfunction "VLED+_9") (pintype "bidirectional"))
      (node (ref "U5") (pin "4") (pinfunction "IN_4") (pintype "power_in"))
      (node (ref "U6") (pin "4") (pinfunction "IN_4") (pintype "power_in"))
      (node (ref "VBUS") (pin "P$1") (pinfunction "1_P$1") (pintype "bidirectional"))
    )
    (net (code "95") (name "VDD") (class "Default")
      (node (ref "C11") (pin "2") (pinfunction "2_2") (pintype "passive"))
      (node (ref "C19") (pin "1") (pinfunction "1_1") (pintype "passive"))
      (node (ref "C20") (pin "1") (pinfunction "1_1") (pintype "passive"))
      (node (ref "C45") (pin "2") (pinfunction "2_2") (pintype "passive"))
      (node (ref "C46") (pin "2") (pinfunction "2_2") (pintype "passive"))
      (node (ref "D4") (pin "C") (pinfunction "C_C") (pintype "passive"))
      (node (ref "IC13") (pin "A22") (pinfunction "VDD_1_A22") (pintype "bidirectional"))
      (node (ref "IC13") (pin "AD14") (pinfunction "VDD_4_AD14") (pintype "bidirectional"))
      (node (ref "IC13") (pin "AD23") (pinfunction "VDD_5_AD23") (pintype "bidirectional"))
      (node (ref "IC13") (pin "B1") (pinfunction "VDD_2_B1") (pintype "bidirectional"))
      (node (ref "IC13") (pin "W1") (pinfunction "VDD_3_W1") (pintype "bidirectional"))
      (node (ref "JP22") (pin "2") (pinfunction "2_2") (pintype "passive"))
      (node (ref "JP24") (pin "2") (pinfunction "2_2") (pintype "passive"))
      (node (ref "JP28") (pin "2") (pinfunction "2_2") (pintype "passive"))
      (node (ref "JP30") (pin "2") (pinfunction "2_2") (pintype "passive"))
      (node (ref "JP34") (pin "2") (pinfunction "2_2") (pintype "passive"))
      (node (ref "JP35") (pin "2") (pinfunction "2_2") (pintype "passive"))
      (node (ref "JP8") (pin "6") (pinfunction "6_6") (pintype "passive"))
      (node (ref "L5") (pin "2") (pinfunction "2_2") (pintype "passive"))
      (node (ref "Q3") (pin "1") (pinfunction "G_1") (pintype "bidirectional"))
      (node (ref "R17") (pin "1") (pinfunction "1_1") (pintype "passive"))
      (node (ref "R7") (pin "1") (pinfunction "1_1") (pintype "passive"))
      (node (ref "R8") (pin "1") (pinfunction "1_1") (pintype "passive"))
      (node (ref "VDD") (pin "P$1") (pinfunction "1_P$1") (pintype "bidirectional"))
    )
    (net (code "96") (name "VDDH") (class "Default")
      (node (ref "IC13") (pin "Y2") (pinfunction "VDDH_Y2") (pintype "bidirectional"))
      (node (ref "JP33") (pin "2") (pinfunction "2_2") (pintype "passive"))
      (node (ref "JP35") (pin "1") (pinfunction "1_1") (pintype "passive"))
    )
    (net (code "97") (name "VUSB") (class "Default")
      (node (ref "C12") (pin "1") (pinfunction "1_1") (pintype "passive"))
      (node (ref "C21") (pin "1") (pinfunction "1_1") (pintype "passive"))
      (node (ref "J1") (pin "A4/B9") (pinfunction "VBUS_A4/B9") (pintype "power_in"))
      (node (ref "J1") (pin "B4/A9") (pinfunction "VBUS_B4/A9") (pintype "power_in"))
      (node (ref "JP12") (pin "2") (pinfunction "2_2") (pintype "passive"))
      (node (ref "U3") (pin "7") (pinfunction "REGIN_7") (pintype "power_in"))
      (node (ref "U3") (pin "8") (pinfunction "VBUS_8") (pintype "power_in"))
    )
    (net (code "98") (name "XC1") (class "Default")
      (node (ref "C10") (pin "2") (pinfunction "2_2") (pintype "passive"))
      (node (ref "IC13") (pin "B24") (pinfunction "XC1_B24") (pintype "bidirectional"))
      (node (ref "Y4") (pin "1") (pinfunction "IN/OUT_1") (pintype "bidirectional"))
    )
    (net (code "99") (name "XC2") (class "Default")
      (node (ref "C9") (pin "2") (pinfunction "2_2") (pintype "passive"))
      (node (ref "IC13") (pin "A23") (pinfunction "XC2_A23") (pintype "bidirectional"))
      (node (ref "Y4") (pin "3") (pinfunction "OUT/IN_3") (pintype "bidirectional"))
    )
    (net (code "100") (name "XL1") (class "Default")
      (node (ref "C6") (pin "2") (pinfunction "2_2") (pintype "passive"))
      (node (ref "IC13") (pin "D2") (pinfunction "P0.00__XL1_D2") (pintype "bidirectional"))
      (node (ref "Y1") (pin "1") (pinfunction "CRYSTAL_1_1") (pintype "bidirectional"))
    )
    (net (code "101") (name "XL2") (class "Default")
      (node (ref "C13") (pin "2") (pinfunction "2_2") (pintype "passive"))
      (node (ref "IC13") (pin "F2") (pinfunction "P0.01__XL2_F2") (pintype "bidirectional"))
      (node (ref "Y1") (pin "2") (pinfunction "CRYSTAL_2_2") (pintype "bidirectional"))
    )
    (net (code "102") (name "unconnected-(E1-NC-Pad2)") (class "Default")
      (node (ref "E1") (pin "2") (pinfunction "NC_2") (pintype "no_connect"))
    )
    (net (code "103") (name "unconnected-(IC6-NC-Pad1)") (class "Default")
      (node (ref "IC6") (pin "1") (pinfunction "NC_1") (pintype "no_connect"))
    )
    (net (code "104") (name "unconnected-(IC8-OCSB-Pad10)") (class "Default")
      (node (ref "IC8") (pin "10") (pinfunction "OCSB_10") (pintype "bidirectional"))
    )
    (net (code "105") (name "unconnected-(IC8-OSDO-Pad11)") (class "Default")
      (node (ref "IC8") (pin "11") (pinfunction "OSDO_11") (pintype "bidirectional"))
    )
    (net (code "106") (name "unconnected-(IC12-TS{slash}MR-PadD1)") (class "Default")
      (node (ref "IC12") (pin "D1") (pinfunction "TS/MR_D1") (pintype "bidirectional"))
    )
    (net (code "107") (name "unconnected-(IC13-DEC5-PadN24)") (class "Default")
      (node (ref "IC13") (pin "N24") (pinfunction "DEC5_N24") (pintype "bidirectional"))
    )
    (net (code "108") (name "unconnected-(IC13-P0.02__AIN0-PadA12)") (class "Default")
      (node (ref "IC13") (pin "A12") (pinfunction "P0.02__AIN0_A12") (pintype "bidirectional"))
    )
    (net (code "109") (name "unconnected-(IC13-P0.09__NFC1-PadL24)") (class "Default")
      (node (ref "IC13") (pin "L24") (pinfunction "P0.09__NFC1_L24") (pintype "bidirectional"))
    )
    (net (code "110") (name "unconnected-(IC13-P0.16-PadAC11)") (class "Default")
      (node (ref "IC13") (pin "AC11") (pinfunction "P0.16_AC11") (pintype "bidirectional"))
    )
    (net (code "111") (name "unconnected-(IC13-P0.17-PadAD12)") (class "Default")
      (node (ref "IC13") (pin "AD12") (pinfunction "P0.17_AD12") (pintype "bidirectional"))
    )
    (net (code "112") (name "unconnected-(IC13-P0.20-PadAD16)") (class "Default")
      (node (ref "IC13") (pin "AD16") (pinfunction "P0.20_AD16") (pintype "bidirectional"))
    )
    (net (code "113") (name "unconnected-(IC13-P0.21-PadAC17)") (class "Default")
      (node (ref "IC13") (pin "AC17") (pinfunction "P0.21_AC17") (pintype "bidirectional"))
    )
    (net (code "114") (name "unconnected-(IC13-P0.23-PadAC19)") (class "Default")
      (node (ref "IC13") (pin "AC19") (pinfunction "P0.23_AC19") (pintype "bidirectional"))
    )
    (net (code "115") (name "unconnected-(IC13-P0.29__AIN5-PadA10)") (class "Default")
      (node (ref "IC13") (pin "A10") (pinfunction "P0.29__AIN5_A10") (pintype "bidirectional"))
    )
    (net (code "116") (name "unconnected-(IC13-P0.31__AIN7-PadA8)") (class "Default")
      (node (ref "IC13") (pin "A8") (pinfunction "P0.31__AIN7_A8") (pintype "bidirectional"))
    )
    (net (code "117") (name "unconnected-(IC13-P1.00-PadAD22)") (class "Default")
      (node (ref "IC13") (pin "AD22") (pinfunction "P1.00_AD22") (pintype "bidirectional"))
    )
    (net (code "118") (name "unconnected-(IC13-P1.01-PadY23)") (class "Default")
      (node (ref "IC13") (pin "Y23") (pinfunction "P1.01_Y23") (pintype "bidirectional"))
    )
    (net (code "119") (name "unconnected-(IC13-P1.02-PadW24)") (class "Default")
      (node (ref "IC13") (pin "W24") (pinfunction "P1.02_W24") (pintype "bidirectional"))
    )
    (net (code "120") (name "unconnected-(IC13-P1.03-PadV23)") (class "Default")
      (node (ref "IC13") (pin "V23") (pinfunction "P1.03_V23") (pintype "bidirectional"))
    )
    (net (code "121") (name "unconnected-(IC13-P1.04-PadU24)") (class "Default")
      (node (ref "IC13") (pin "U24") (pinfunction "P1.04_U24") (pintype "bidirectional"))
    )
    (net (code "122") (name "unconnected-(IC13-P1.05-PadT23)") (class "Default")
      (node (ref "IC13") (pin "T23") (pinfunction "P1.05_T23") (pintype "bidirectional"))
    )
    (net (code "123") (name "unconnected-(IC13-P1.06-PadR24)") (class "Default")
      (node (ref "IC13") (pin "R24") (pinfunction "P1.06_R24") (pintype "bidirectional"))
    )
    (net (code "124") (name "unconnected-(IC13-P1.07-PadP23)") (class "Default")
      (node (ref "IC13") (pin "P23") (pinfunction "P1.07_P23") (pintype "bidirectional"))
    )
    (net (code "125") (name "unconnected-(IC13-P1.08-PadP2)") (class "Default")
      (node (ref "IC13") (pin "P2") (pinfunction "P1.08_P2") (pintype "bidirectional"))
    )
    (net (code "126") (name "unconnected-(IC13-P1.09-PadR1)") (class "Default")
      (node (ref "IC13") (pin "R1") (pinfunction "P1.09_R1") (pintype "bidirectional"))
    )
    (net (code "127") (name "unconnected-(IC13-P1.10-PadA20)") (class "Default")
      (node (ref "IC13") (pin "A20") (pinfunction "P1.10_A20") (pintype "bidirectional"))
    )
    (net (code "128") (name "unconnected-(IC13-P1.11-PadB19)") (class "Default")
      (node (ref "IC13") (pin "B19") (pinfunction "P1.11_B19") (pintype "bidirectional"))
    )
    (net (code "129") (name "unconnected-(IC13-P1.12-PadB17)") (class "Default")
      (node (ref "IC13") (pin "B17") (pinfunction "P1.12_B17") (pintype "bidirectional"))
    )
    (net (code "130") (name "unconnected-(IC13-P1.13-PadA16)") (class "Default")
      (node (ref "IC13") (pin "A16") (pinfunction "P1.13_A16") (pintype "bidirectional"))
    )
    (net (code "131") (name "unconnected-(IC13-P1.14-PadB15)") (class "Default")
      (node (ref "IC13") (pin "B15") (pinfunction "P1.14_B15") (pintype "bidirectional"))
    )
    (net (code "132") (name "unconnected-(IC13-P1.15-PadA14)") (class "Default")
      (node (ref "IC13") (pin "A14") (pinfunction "P1.15_A14") (pintype "bidirectional"))
    )
    (net (code "133") (name "unconnected-(J1-SBU1-PadA8)") (class "Default")
      (node (ref "J1") (pin "A8") (pinfunction "SBU1_A8") (pintype "bidirectional"))
    )
    (net (code "134") (name "unconnected-(J1-SBU2-PadB8)") (class "Default")
      (node (ref "J1") (pin "B8") (pinfunction "SBU2_B8") (pintype "bidirectional"))
    )
    (net (code "135") (name "unconnected-(J2-SBU1-PadA8)") (class "Default")
      (node (ref "J2") (pin "A8") (pinfunction "SBU1_A8") (pintype "bidirectional"))
    )
    (net (code "136") (name "unconnected-(J2-SBU2-PadB8)") (class "Default")
      (node (ref "J2") (pin "B8") (pinfunction "SBU2_B8") (pintype "bidirectional"))
    )
    (net (code "137") (name "unconnected-(U$6-DAT1-Pad7)") (class "Default")
      (node (ref "U$6") (pin "7") (pinfunction "DAT1_7") (pintype "bidirectional"))
    )
    (net (code "138") (name "unconnected-(U$6-DAT2-Pad1)") (class "Default")
      (node (ref "U$6") (pin "1") (pinfunction "DAT2_1") (pintype "input"))
    )
    (net (code "139") (name "unconnected-(U$6-EP-Pad9)") (class "Default")
      (node (ref "U$6") (pin "9") (pinfunction "EP_9") (pintype "passive"))
    )
    (net (code "140") (name "unconnected-(U3A-#SUSPEND-Pad15)") (class "Default")
      (node (ref "U3") (pin "15") (pinfunction "#SUSPEND_15") (pintype "output"))
    )
    (net (code "141") (name "unconnected-(U3A-CTS-Pad18)") (class "Default")
      (node (ref "U3") (pin "18") (pinfunction "CTS_18") (pintype "input"))
    )
    (net (code "142") (name "unconnected-(U3A-DCD-Pad24)") (class "Default")
      (node (ref "U3") (pin "24") (pinfunction "DCD_24") (pintype "input"))
    )
    (net (code "143") (name "unconnected-(U3A-DSR-Pad22)") (class "Default")
      (node (ref "U3") (pin "22") (pinfunction "DSR_22") (pintype "input"))
    )
    (net (code "144") (name "unconnected-(U3A-GPIO2-Pad12)") (class "Default")
      (node (ref "U3") (pin "12") (pinfunction "GPIO2_12") (pintype "bidirectional"))
    )
    (net (code "145") (name "unconnected-(U3A-GPIO3-Pad11)") (class "Default")
      (node (ref "U3") (pin "11") (pinfunction "GPIO3_11") (pintype "bidirectional"))
    )
    (net (code "146") (name "unconnected-(U3A-NC-Pad10)") (class "Default")
      (node (ref "U3") (pin "10") (pinfunction "NC_10") (pintype "no_connect"))
    )
    (net (code "147") (name "unconnected-(U3A-RI-Pad1)") (class "Default")
      (node (ref "U3") (pin "1") (pinfunction "RI_1") (pintype "input"))
    )
    (net (code "148") (name "unconnected-(U3A-RTS-Pad19)") (class "Default")
      (node (ref "U3") (pin "19") (pinfunction "RTS_19") (pintype "output"))
    )
    (net (code "149") (name "unconnected-(U3A-SUSPEND-Pad17)") (class "Default")
      (node (ref "U3") (pin "17") (pinfunction "SUSPEND_17") (pintype "output"))
    )
    (net (code "150") (name "unconnected-(Y4-NC-Pad4)") (class "Default")
      (node (ref "Y4") (pin "4") (pinfunction "NC_4") (pintype "no_connect"))
    )
  )
)
